# Dataforge-Pi.net
KiCad netlist of a schematic drawn in EAGLE
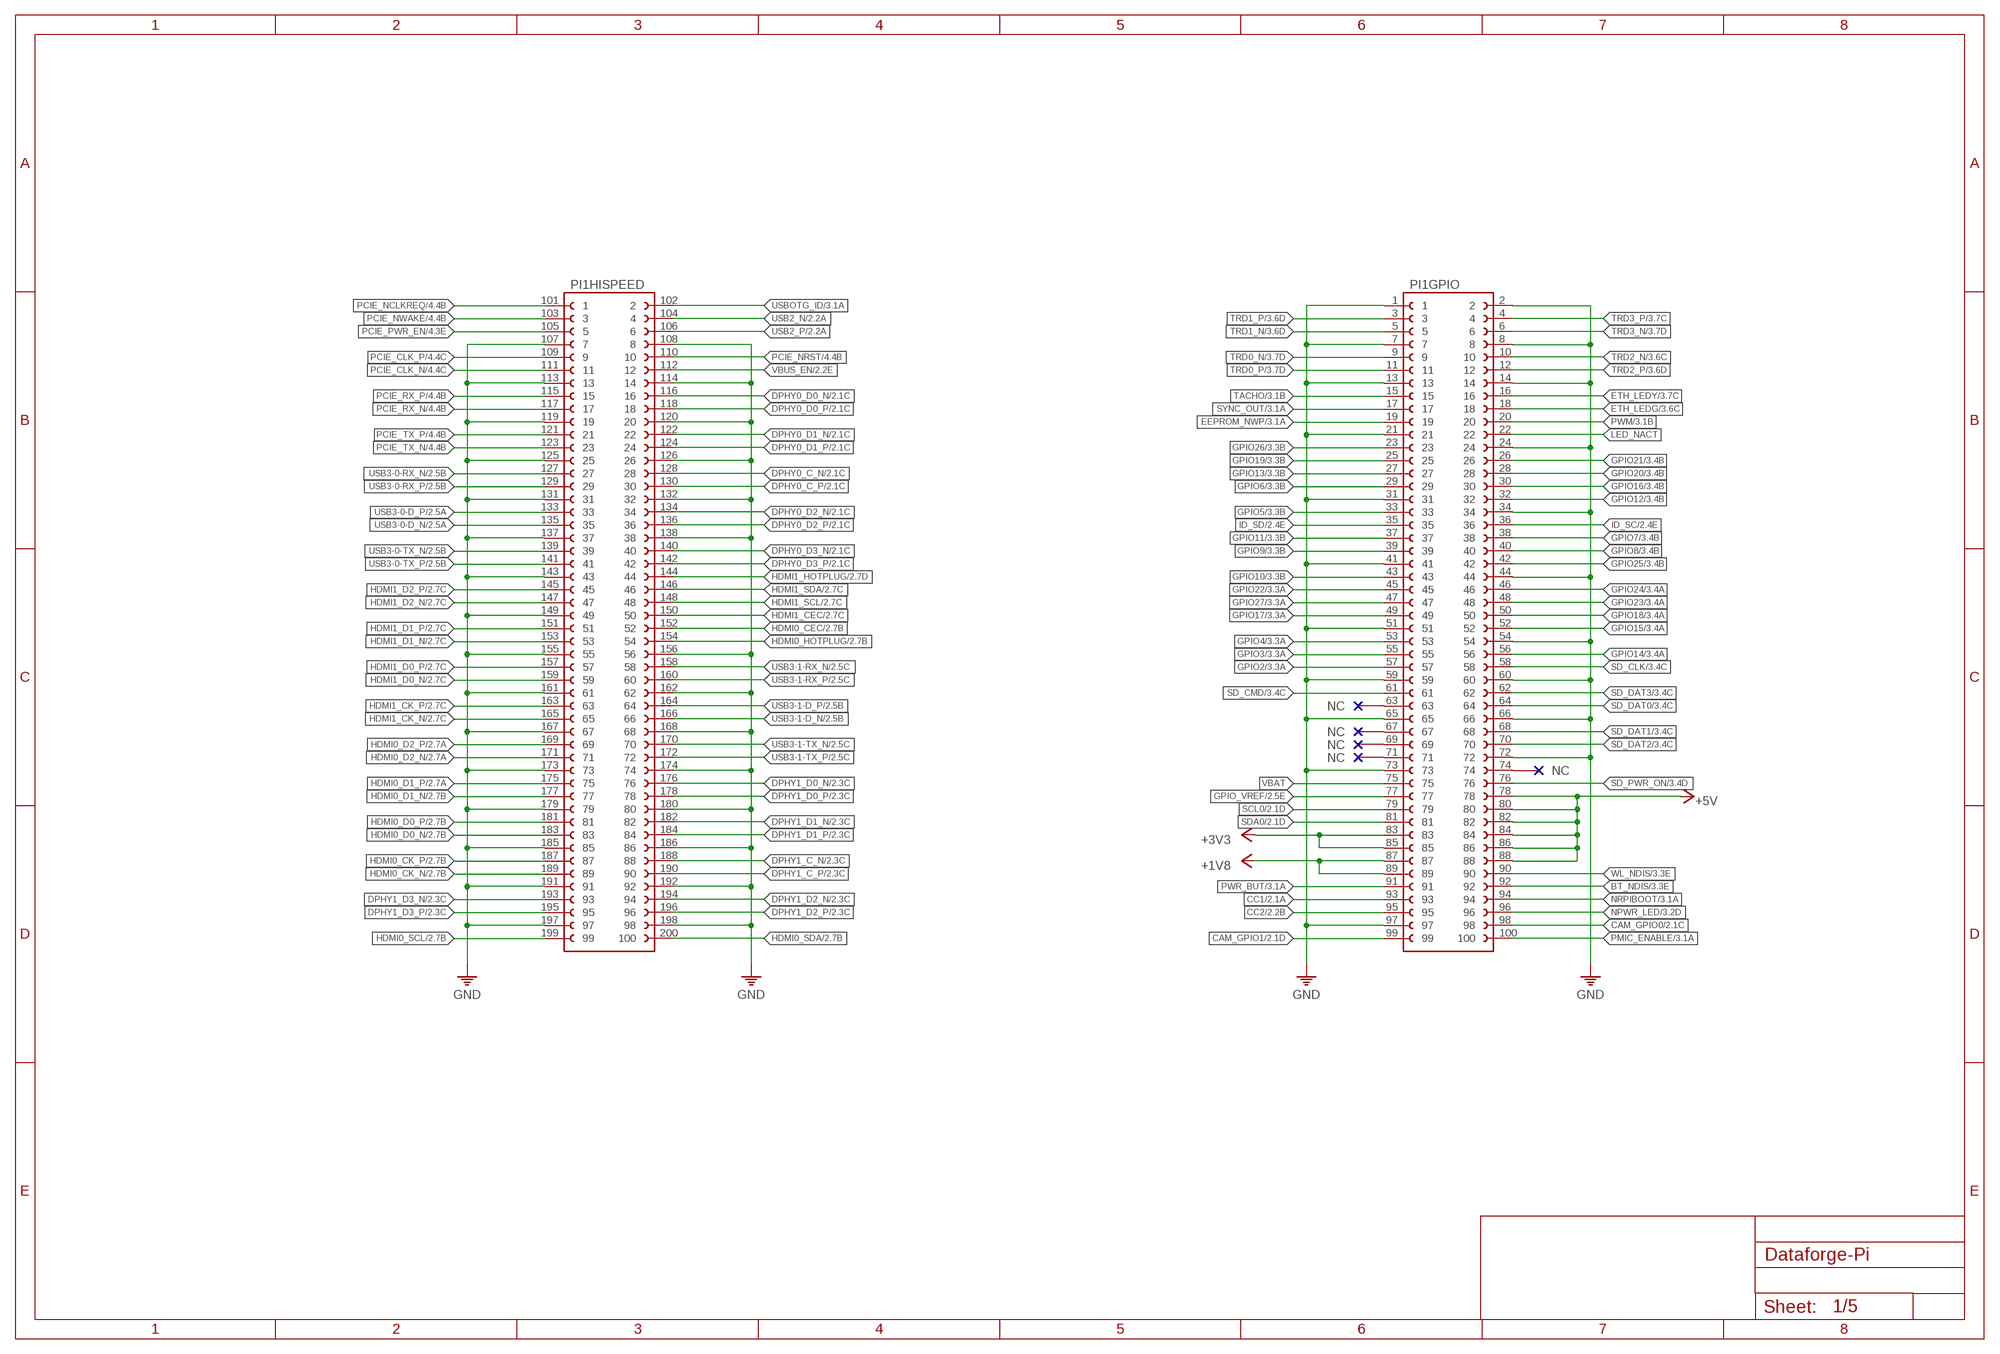
[diagram p0: schematic, sheet 1]
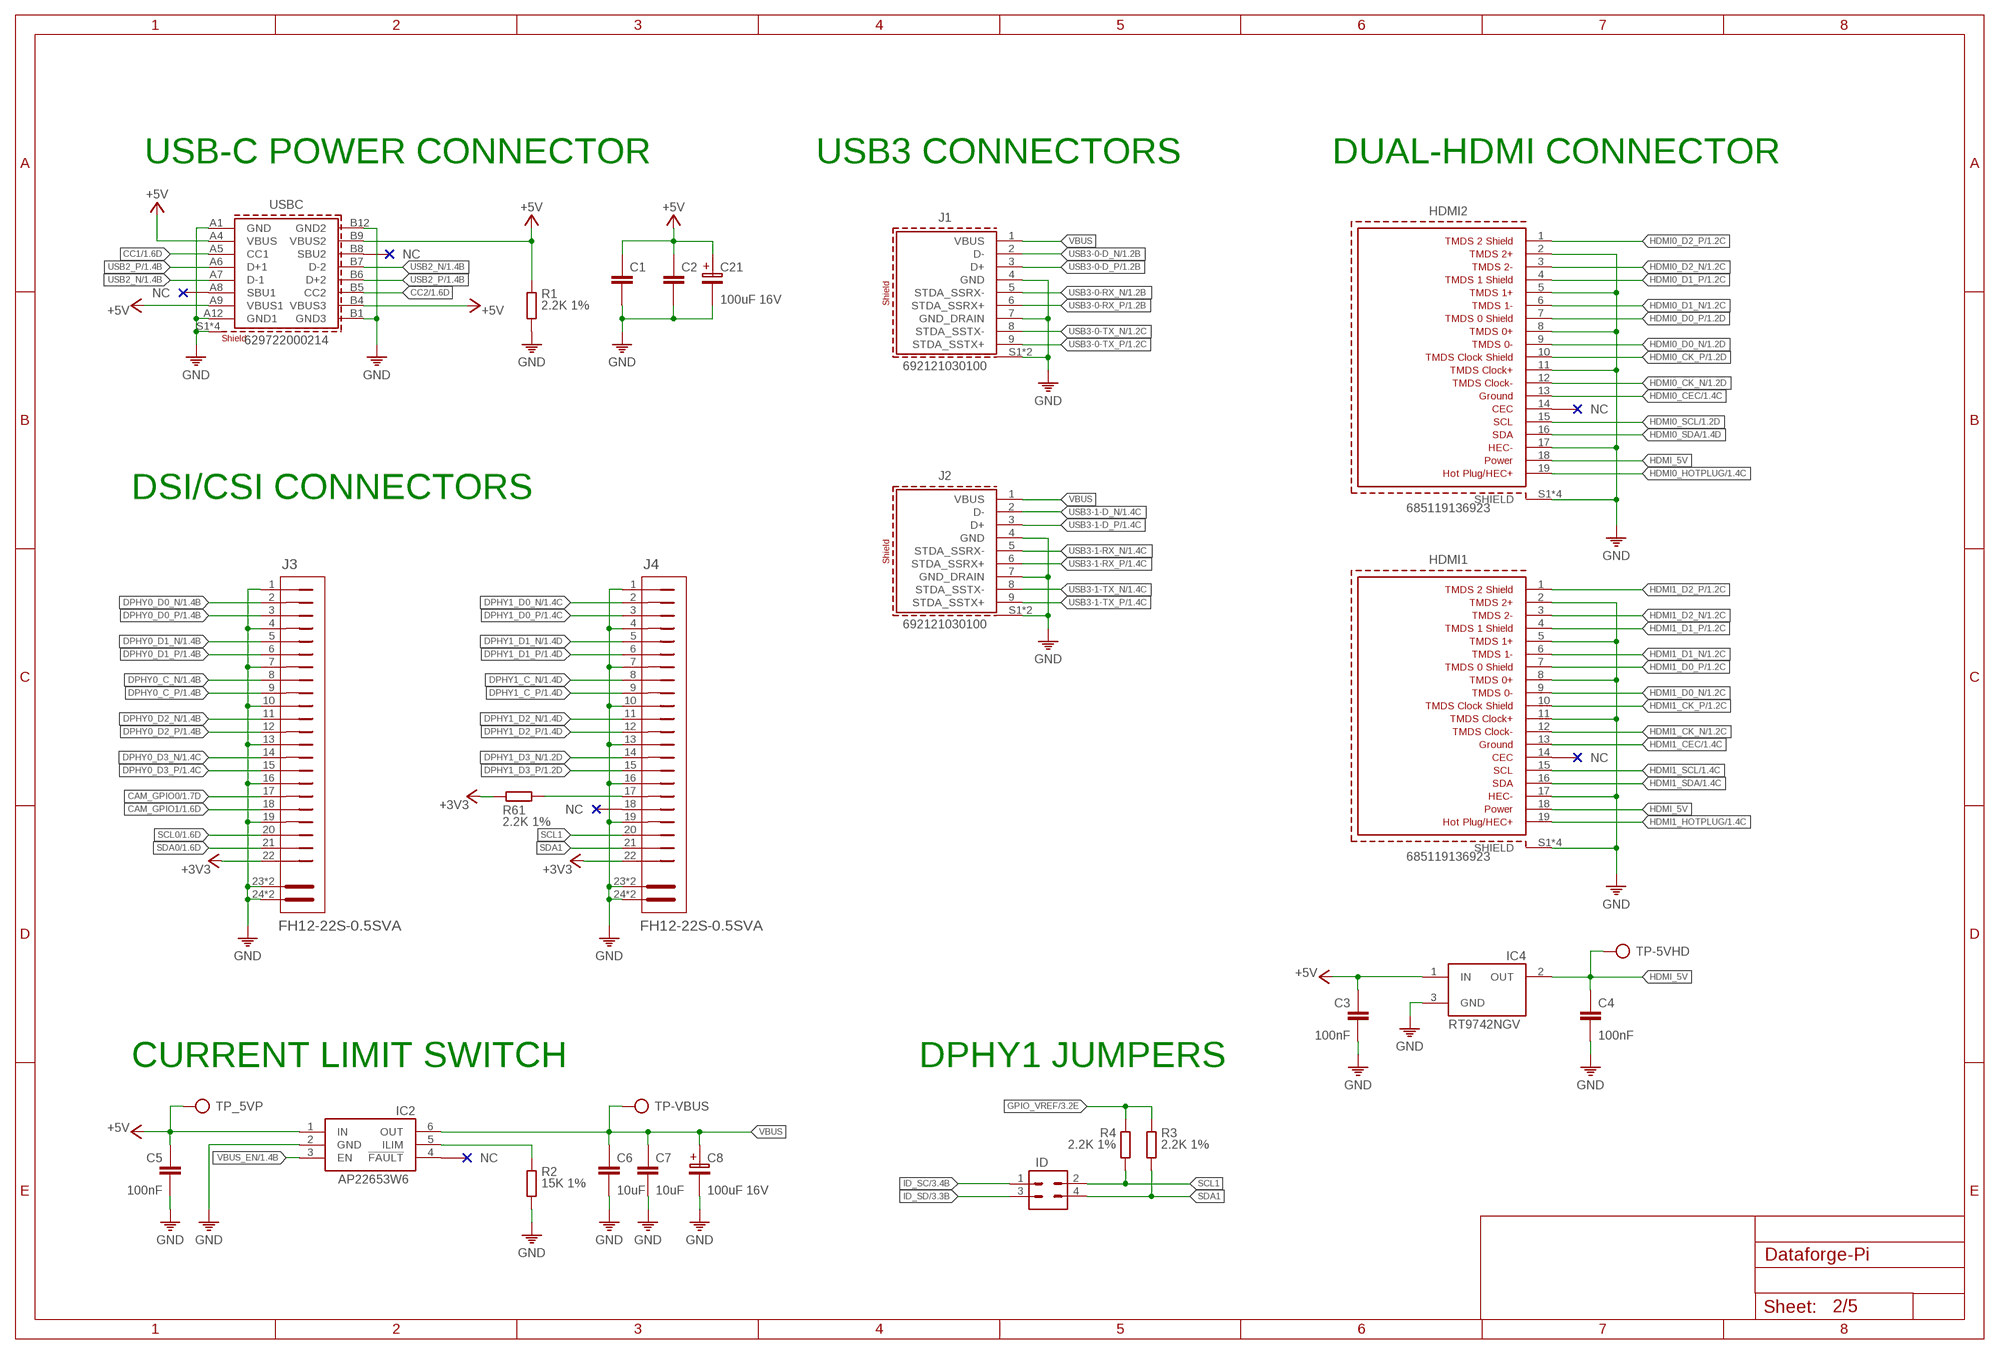
[diagram p1: schematic, sheet 2]
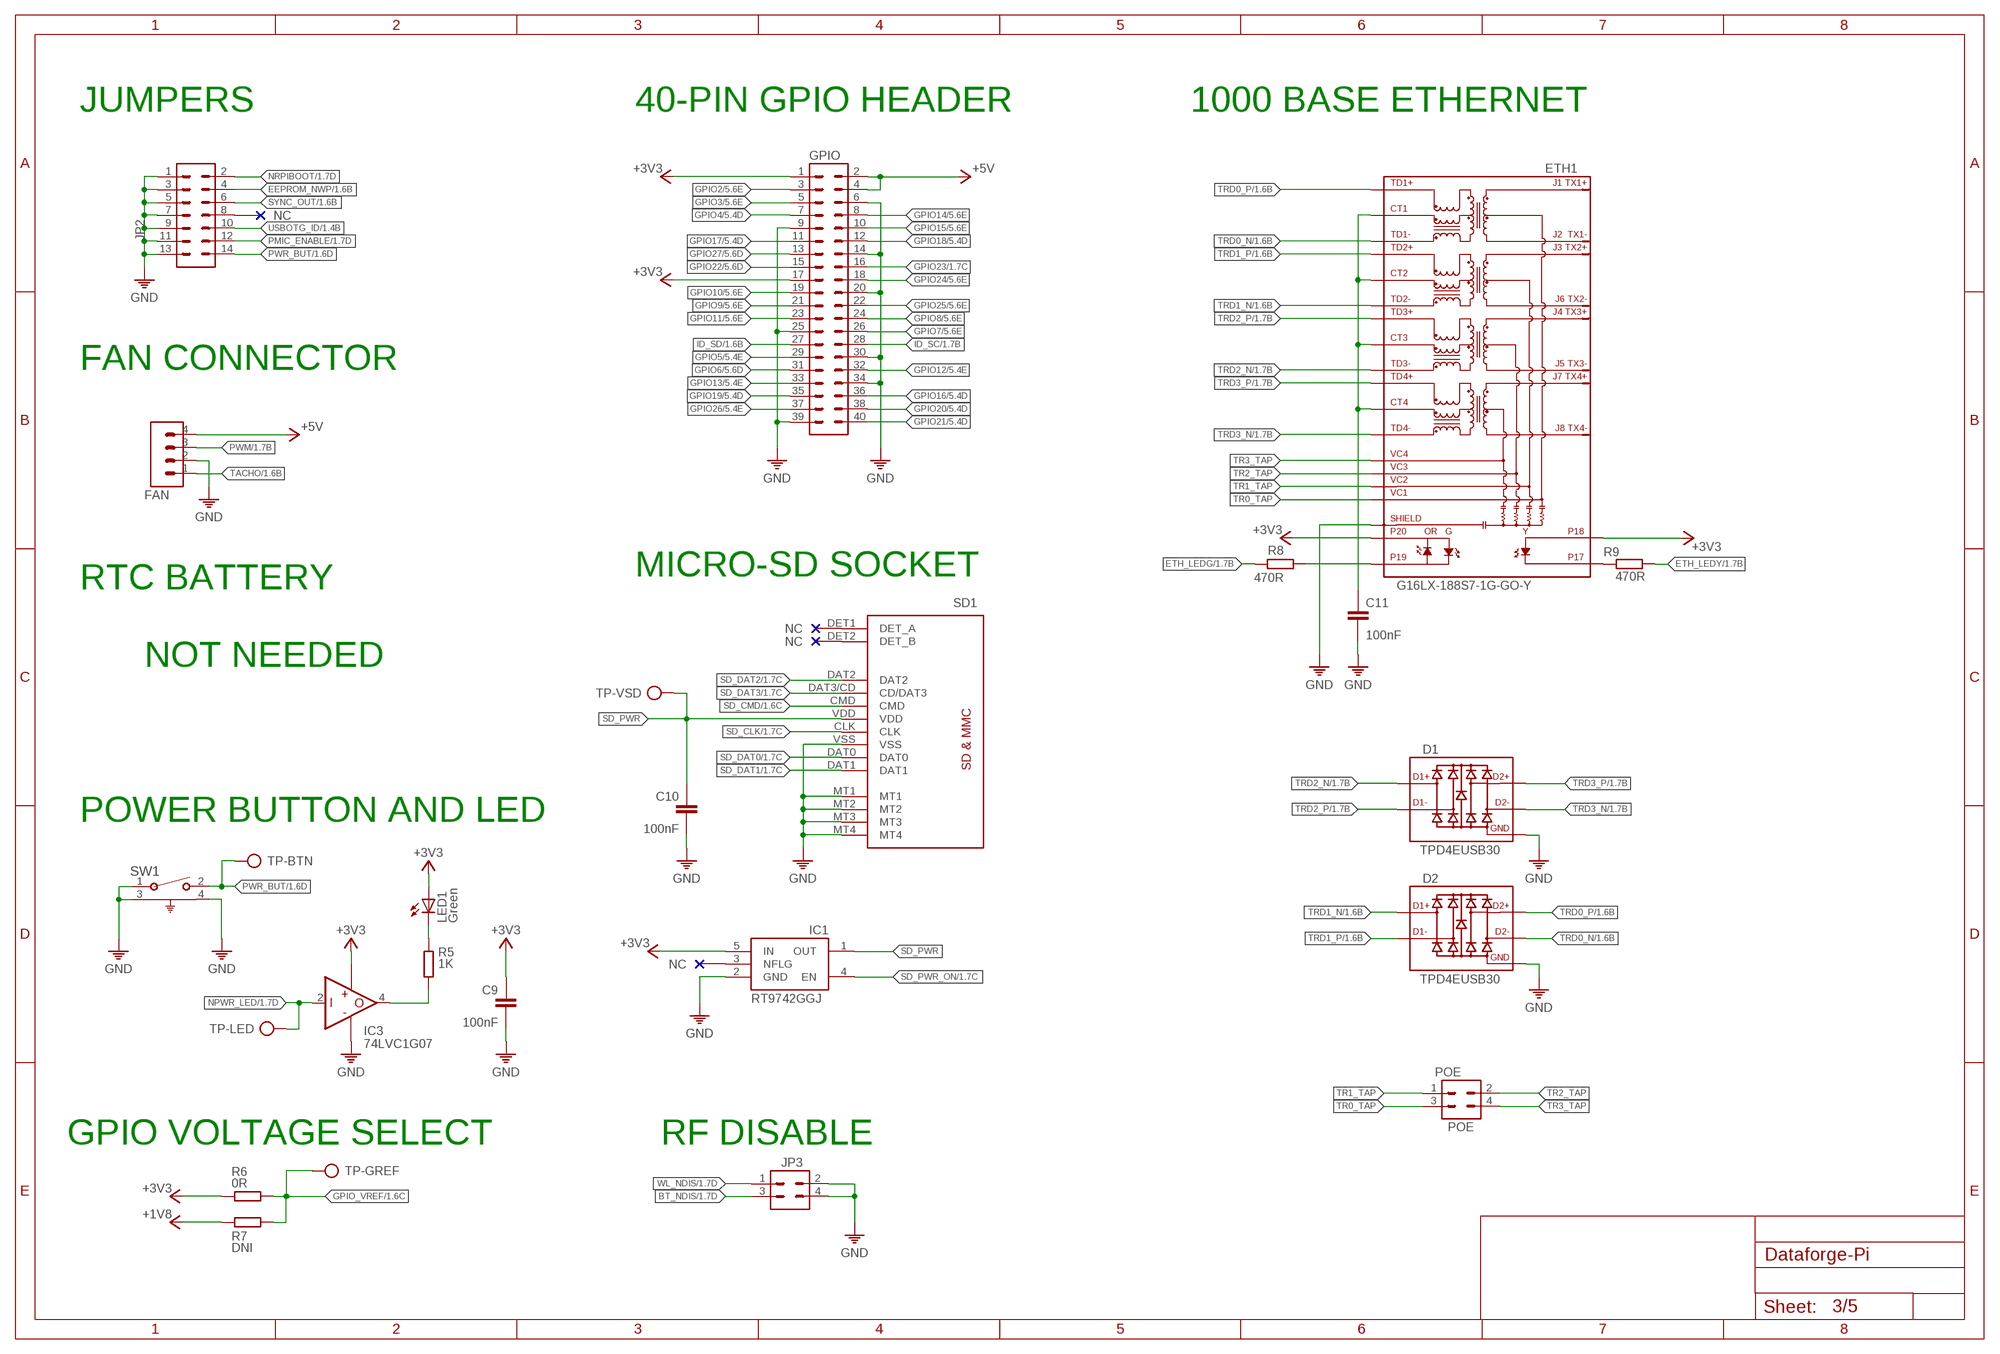
[diagram p2: schematic, sheet 3]
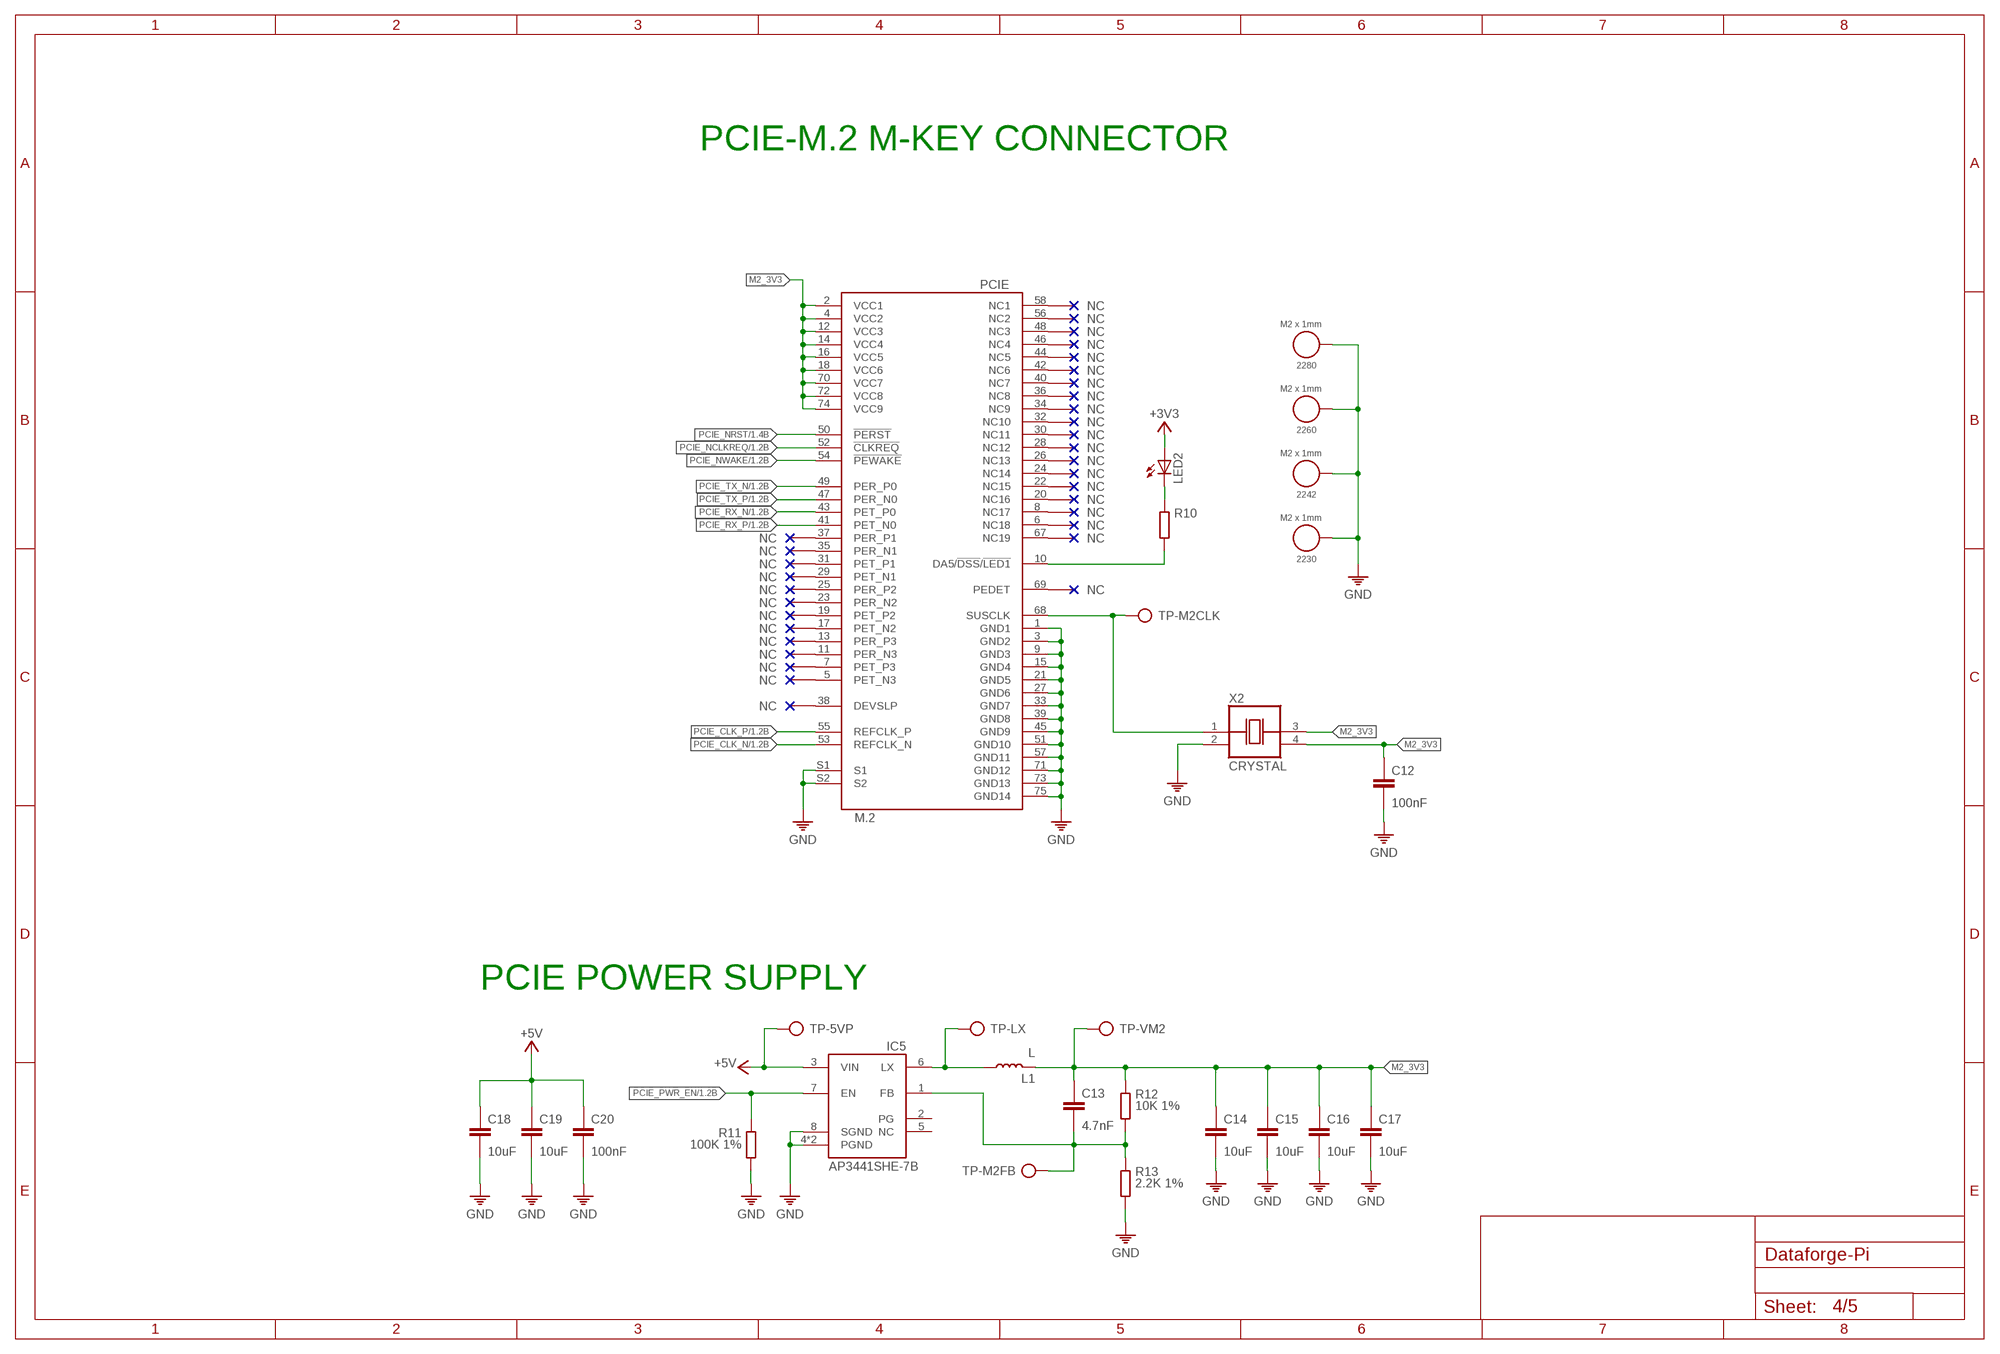
[diagram p3: schematic, sheet 4]
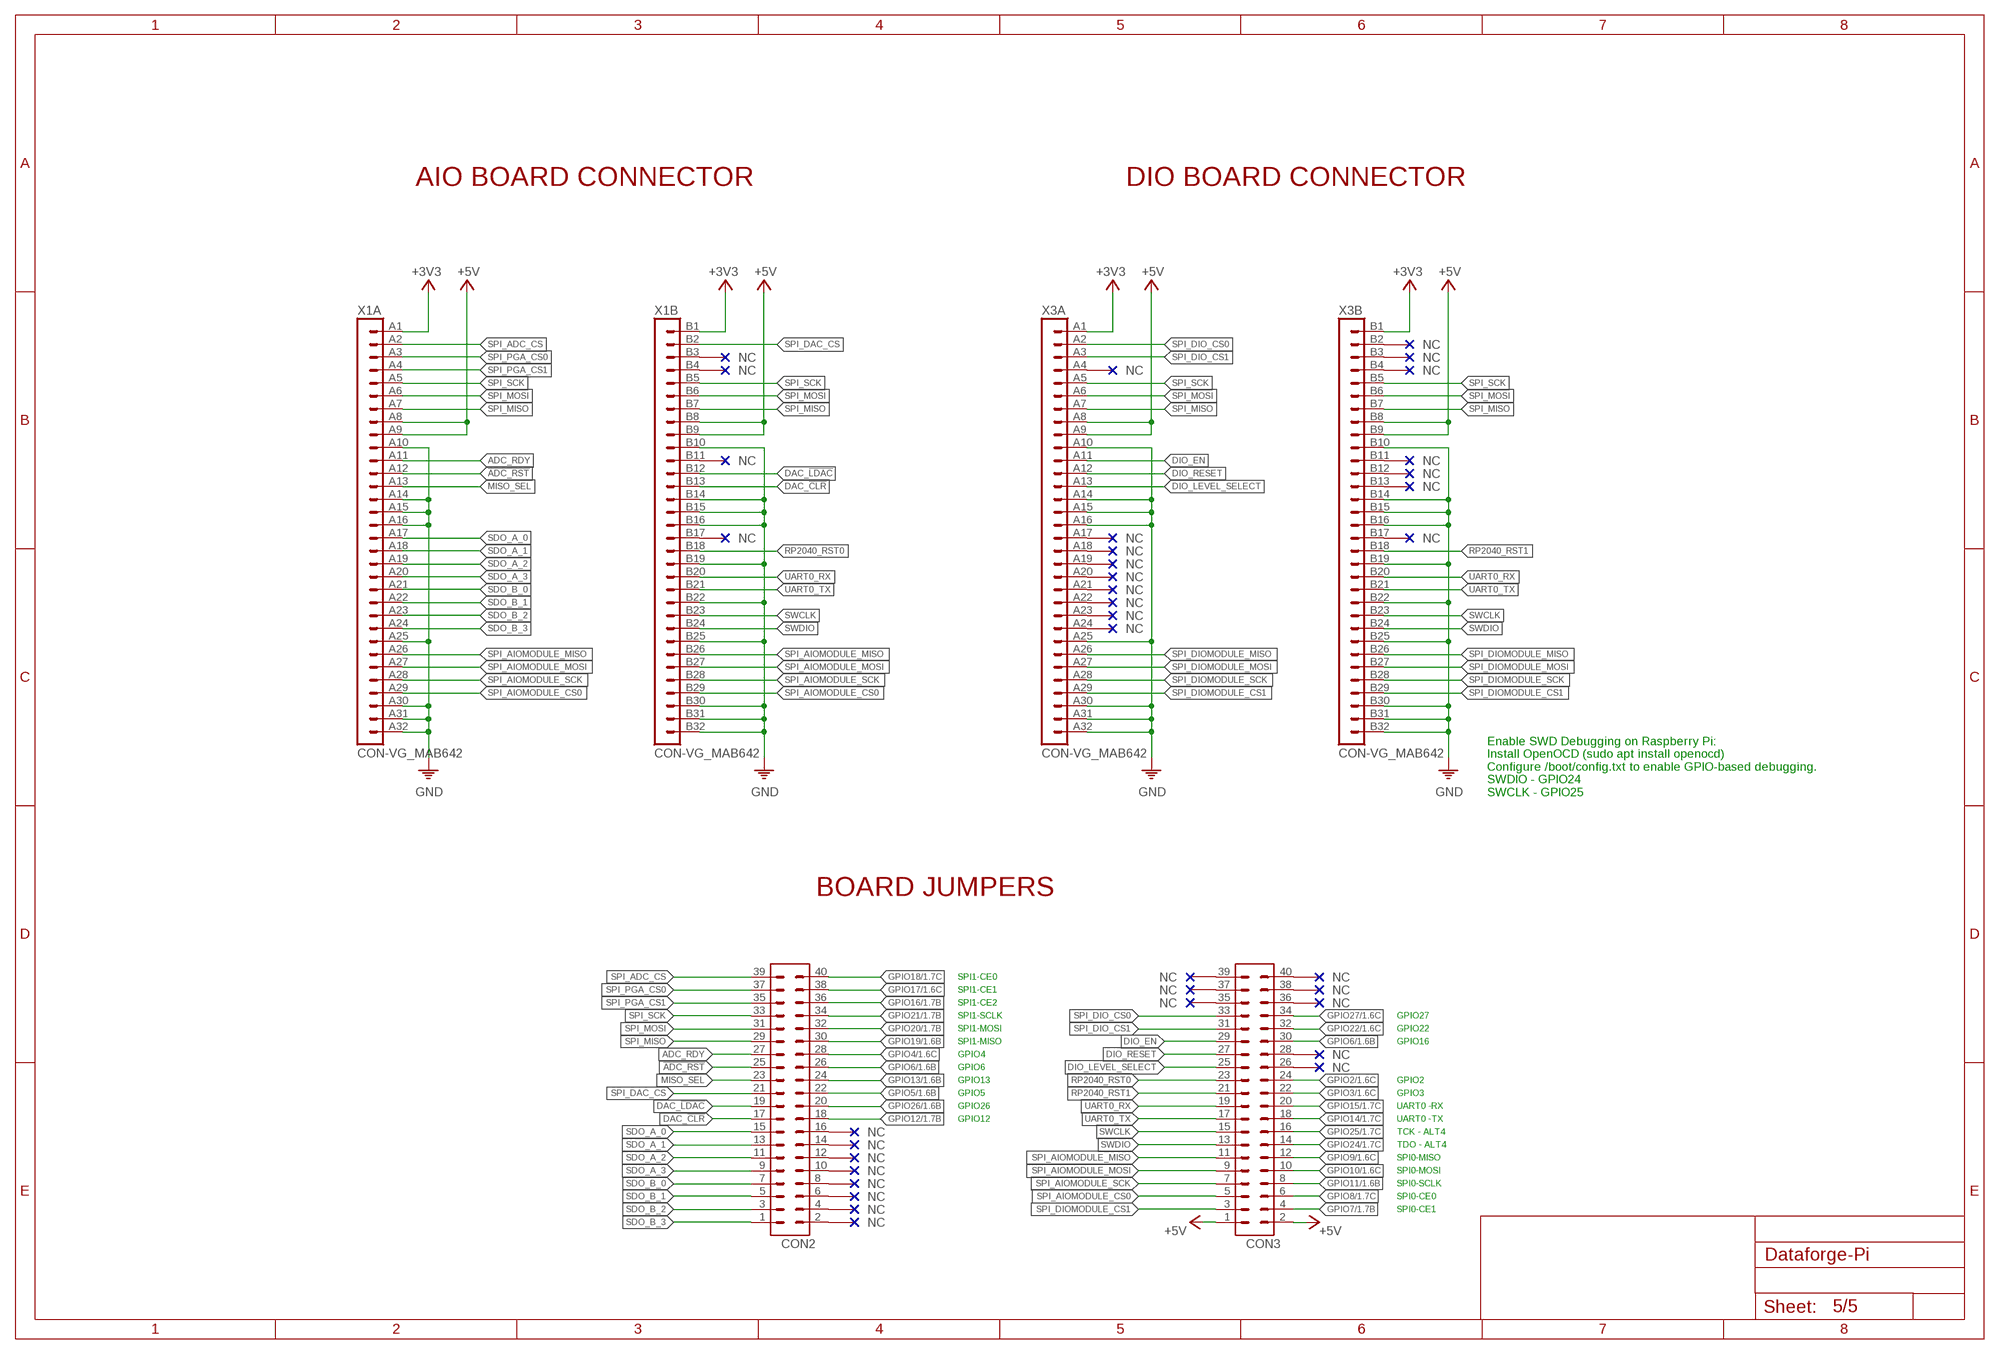
[diagram p4: schematic, sheet 5]

(export (version "E")
  (design (tool "Eeschema 10.0.6"))
  (components
    (comp (ref "C9")
      (value "100nF")
      (footprint "eagle-import:0402")
      (libsource (lib "eagle-import") (part "C0402"))
    )
    (comp (ref "C10")
      (value "100nF")
      (footprint "eagle-import:0402")
      (libsource (lib "eagle-import") (part "C0402"))
    )
    (comp (ref "C11")
      (value "100nF")
      (footprint "eagle-import:0402")
      (libsource (lib "eagle-import") (part "C0402"))
    )
    (comp (ref "D1")
      (value "TPD4EUSB30")
      (footprint "eagle-import:USON")
      (libsource (lib "eagle-import") (part "TPD4EUSB30"))
    )
    (comp (ref "D2")
      (value "TPD4EUSB30")
      (footprint "eagle-import:USON")
      (libsource (lib "eagle-import") (part "TPD4EUSB30"))
    )
    (comp (ref "ETH1")
      (value "G16LX-188S7-1G-GO-Y")
      (footprint "eagle-import:MAGJACK_POE")
      (libsource (lib "eagle-import") (part "MAGJACK-POE"))
    )
    (comp (ref "FAN")
      (value "CON-1X4")
      (footprint "eagle-import:1X4")
      (libsource (lib "eagle-import") (part "CON-1X4"))
    )
    (comp (ref "GPIO")
      (value "CON-2X20")
      (footprint "eagle-import:2X20")
      (libsource (lib "eagle-import") (part "CON-2X20"))
    )
    (comp (ref "IC1")
      (value "RT9742GGJ")
      (footprint "eagle-import:SOT23-5")
      (libsource (lib "eagle-import") (part "RT9742GGJ5"))
    )
    (comp (ref "IC3")
      (value "74LVC1G07")
      (footprint "eagle-import:SOT23-5")
      (libsource (lib "eagle-import") (part "74LVC1G07"))
    )
    (comp (ref "JP2")
      (value "CON-2X7")
      (footprint "eagle-import:2X7")
      (libsource (lib "eagle-import") (part "CON-2X7"))
    )
    (comp (ref "JP3")
      (value "CON-2X2")
      (footprint "eagle-import:2X2")
      (libsource (lib "eagle-import") (part "CON-2X2"))
    )
    (comp (ref "LED1")
      (value "Green")
      (footprint "eagle-import:CHIPLED_0805")
      (libsource (lib "eagle-import") (part "LEDCHIPLED_0805"))
    )
    (comp (ref "POE")
      (value "POE")
      (footprint "eagle-import:2X2")
      (libsource (lib "eagle-import") (part "CON-2X2"))
    )
    (comp (ref "R5")
      (value "1K")
      (footprint "eagle-import:0402")
      (libsource (lib "eagle-import") (part "R0402"))
    )
    (comp (ref "R6")
      (value "0R")
      (footprint "eagle-import:0402")
      (libsource (lib "eagle-import") (part "R0402"))
    )
    (comp (ref "R7")
      (value "DNI")
      (footprint "eagle-import:0402")
      (libsource (lib "eagle-import") (part "R0402"))
    )
    (comp (ref "R8")
      (value "470R")
      (footprint "eagle-import:0402")
      (libsource (lib "eagle-import") (part "R0402"))
    )
    (comp (ref "R9")
      (value "470R")
      (footprint "eagle-import:0402")
      (libsource (lib "eagle-import") (part "R0402"))
    )
    (comp (ref "SD1")
      (value "MICRO-SD")
      (footprint "eagle-import:MICROSD")
      (libsource (lib "eagle-import") (part "MICRO-SD"))
    )
    (comp (ref "SW1")
      (value "1825027-8")
      (footprint "eagle-import:SW2_1825027-C_TEC")
      (fields (field (name "COPYRIGHT") "Copyright (C) 2025 Ultra Librarian. All rights reserved."))
      (libsource (lib "eagle-import") (part "1825027-8"))
    )
    (comp (ref "TP-BTN")
      (value "TP")
      (footprint "eagle-import:TP")
      (libsource (lib "eagle-import") (part "TP"))
    )
    (comp (ref "TP-GREF")
      (value "TP")
      (footprint "eagle-import:TP")
      (libsource (lib "eagle-import") (part "TP"))
    )
    (comp (ref "TP-LED")
      (value "TP")
      (footprint "eagle-import:TP")
      (libsource (lib "eagle-import") (part "TP"))
    )
    (comp (ref "TP-VSD")
      (value "TP")
      (footprint "eagle-import:TP")
      (libsource (lib "eagle-import") (part "TP"))
    )
    (comp (ref "2230")
      (value "M2 x 1mm")
      (footprint "eagle-import:WA-SMSI_9774010243")
      (libsource (lib "eagle-import") (part "WA-SMSI_9774XXX243_9774010243"))
    )
    (comp (ref "2242")
      (value "M2 x 1mm")
      (footprint "eagle-import:WA-SMSI_9774010243")
      (libsource (lib "eagle-import") (part "WA-SMSI_9774XXX243_9774010243"))
    )
    (comp (ref "2260")
      (value "M2 x 1mm")
      (footprint "eagle-import:WA-SMSI_9774010243")
      (libsource (lib "eagle-import") (part "WA-SMSI_9774XXX243_9774010243"))
    )
    (comp (ref "2280")
      (value "M2 x 1mm")
      (footprint "eagle-import:WA-SMSI_9774010243")
      (libsource (lib "eagle-import") (part "WA-SMSI_9774XXX243_9774010243"))
    )
    (comp (ref "C12")
      (value "100nF")
      (footprint "eagle-import:0402")
      (libsource (lib "eagle-import") (part "C0402"))
    )
    (comp (ref "C13")
      (value "4.7nF")
      (footprint "eagle-import:0402")
      (libsource (lib "eagle-import") (part "C0402"))
    )
    (comp (ref "C14")
      (value "10uF")
      (footprint "eagle-import:0805")
      (libsource (lib "eagle-import") (part "C0805"))
    )
    (comp (ref "C15")
      (value "10uF")
      (footprint "eagle-import:0805")
      (libsource (lib "eagle-import") (part "C0805"))
    )
    (comp (ref "C16")
      (value "10uF")
      (footprint "eagle-import:0805")
      (libsource (lib "eagle-import") (part "C0805"))
    )
    (comp (ref "C17")
      (value "10uF")
      (footprint "eagle-import:0805")
      (libsource (lib "eagle-import") (part "C0805"))
    )
    (comp (ref "C18")
      (value "10uF")
      (footprint "eagle-import:0805")
      (libsource (lib "eagle-import") (part "C0805"))
    )
    (comp (ref "C19")
      (value "10uF")
      (footprint "eagle-import:0805")
      (libsource (lib "eagle-import") (part "C0805"))
    )
    (comp (ref "C20")
      (value "100nF")
      (footprint "eagle-import:0402")
      (libsource (lib "eagle-import") (part "C0402"))
    )
    (comp (ref "IC5")
      (value "AP3441SHE-7B")
      (footprint "eagle-import:SON50P201X201X56-9T90X170N")
      (libsource (lib "eagle-import") (part "AP3441SHE-7B"))
    )
    (comp (ref "L1")
      (value "L")
      (footprint "eagle-import:SRR5228A")
      (libsource (lib "eagle-import") (part "L"))
    )
    (comp (ref "LED2")
      (value "LEDCHIPLED_0805")
      (footprint "eagle-import:CHIPLED_0805")
      (libsource (lib "eagle-import") (part "LEDCHIPLED_0805"))
    )
    (comp (ref "PCIE")
      (value "M.2")
      (footprint "eagle-import:M.2")
      (libsource (lib "eagle-import") (part "M.2"))
    )
    (comp (ref "R10")
      (value "R0402")
      (footprint "eagle-import:0402")
      (libsource (lib "eagle-import") (part "R0402"))
    )
    (comp (ref "R11")
      (value "100K 1%")
      (footprint "eagle-import:0402")
      (libsource (lib "eagle-import") (part "R0402"))
    )
    (comp (ref "R12")
      (value "10K 1%")
      (footprint "eagle-import:0402")
      (libsource (lib "eagle-import") (part "R0402"))
    )
    (comp (ref "R13")
      (value "2.2K 1%")
      (footprint "eagle-import:0402")
      (libsource (lib "eagle-import") (part "R0402"))
    )
    (comp (ref "TP-5VP")
      (value "TP")
      (footprint "eagle-import:TP")
      (libsource (lib "eagle-import") (part "TP"))
    )
    (comp (ref "TP-LX")
      (value "TP")
      (footprint "eagle-import:TP")
      (libsource (lib "eagle-import") (part "TP"))
    )
    (comp (ref "TP-M2CLK")
      (value "TP")
      (footprint "eagle-import:TP")
      (libsource (lib "eagle-import") (part "TP"))
    )
    (comp (ref "TP-M2FB")
      (value "TP")
      (footprint "eagle-import:TP")
      (libsource (lib "eagle-import") (part "TP"))
    )
    (comp (ref "TP-VM2")
      (value "TP")
      (footprint "eagle-import:TP")
      (libsource (lib "eagle-import") (part "TP"))
    )
    (comp (ref "X2")
      (value "CRYSTAL")
      (footprint "eagle-import:OSCCC500X320X130")
      (libsource (lib "eagle-import") (part "CRYSTAL"))
    )
    (comp (ref "PI1")
      (value "RASPBERRY_CM5")
      (footprint "eagle-import:CM5")
      (libsource (lib "eagle-import") (part "RASPBERRY_CM5"))
    )
    (comp (ref "CON2")
      (value "CON-2X20")
      (footprint "eagle-import:2X20")
      (libsource (lib "eagle-import") (part "CON-2X20"))
    )
    (comp (ref "CON3")
      (value "CON-2X20")
      (footprint "eagle-import:2X20")
      (libsource (lib "eagle-import") (part "CON-2X20"))
    )
    (comp (ref "X1")
      (value "CON-VG_MAB642")
      (footprint "eagle-import:CON-VG-MAB64-RECEPTACLE")
      (libsource (lib "eagle-import") (part "CON-VG_MAB642"))
    )
    (comp (ref "X3")
      (value "CON-VG_MAB642")
      (footprint "eagle-import:CON-VG-MAB64-RECEPTACLE")
      (libsource (lib "eagle-import") (part "CON-VG_MAB642"))
    )
    (comp (ref "C1")
      (value "C0402")
      (footprint "eagle-import:0402")
      (libsource (lib "eagle-import") (part "C0402"))
    )
    (comp (ref "C2")
      (value "C0402")
      (footprint "eagle-import:0402")
      (libsource (lib "eagle-import") (part "C0402"))
    )
    (comp (ref "C3")
      (value "100nF")
      (footprint "eagle-import:0402")
      (libsource (lib "eagle-import") (part "C0402"))
    )
    (comp (ref "C4")
      (value "100nF")
      (footprint "eagle-import:0402")
      (libsource (lib "eagle-import") (part "C0402"))
    )
    (comp (ref "C5")
      (value "100nF")
      (footprint "eagle-import:0402")
      (libsource (lib "eagle-import") (part "C0402"))
    )
    (comp (ref "C6")
      (value "10uF")
      (footprint "eagle-import:0805")
      (libsource (lib "eagle-import") (part "C0805"))
    )
    (comp (ref "C7")
      (value "10uF")
      (footprint "eagle-import:0805")
      (libsource (lib "eagle-import") (part "C0805"))
    )
    (comp (ref "C8")
      (value "100uF 16V")
      (footprint "eagle-import:100UF-16V")
      (libsource (lib "eagle-import") (part "CPOL"))
    )
    (comp (ref "C21")
      (value "100uF 16V")
      (footprint "eagle-import:100UF-16V")
      (libsource (lib "eagle-import") (part "CPOL"))
    )
    (comp (ref "HDMI1")
      (value "685119136923")
      (footprint "eagle-import:685119136923")
      (libsource (lib "eagle-import") (part "685119136923"))
    )
    (comp (ref "HDMI2")
      (value "685119136923")
      (footprint "eagle-import:685119136923")
      (libsource (lib "eagle-import") (part "685119136923"))
    )
    (comp (ref "IC2")
      (value "AP22653W6")
      (footprint "eagle-import:SOT23-6")
      (libsource (lib "eagle-import") (part "AP22653W6"))
    )
    (comp (ref "IC4")
      (value "RT9742NGV")
      (footprint "eagle-import:SOT23")
      (libsource (lib "eagle-import") (part "RT9742NGV"))
    )
    (comp (ref "ID")
      (value "CON-2X2")
      (footprint "eagle-import:2X2")
      (libsource (lib "eagle-import") (part "CON-2X2"))
    )
    (comp (ref "J1")
      (value "692121030100")
      (footprint "eagle-import:692121030100")
      (libsource (lib "eagle-import") (part "692121030100"))
    )
    (comp (ref "J2")
      (value "692121030100")
      (footprint "eagle-import:692121030100")
      (libsource (lib "eagle-import") (part "692121030100"))
    )
    (comp (ref "J3")
      (value "FH12-22S-0.5SVA")
      (footprint "eagle-import:FH12-22S-0.5SH")
      (libsource (lib "eagle-import") (part "FH12-22S-0.5SVA"))
    )
    (comp (ref "J4")
      (value "FH12-22S-0.5SVA")
      (footprint "eagle-import:FH12-22S-0.5SH")
      (libsource (lib "eagle-import") (part "FH12-22S-0.5SVA"))
    )
    (comp (ref "R1")
      (value "2.2K 1%")
      (footprint "eagle-import:0402")
      (libsource (lib "eagle-import") (part "R0402"))
    )
    (comp (ref "R2")
      (value "15K 1%")
      (footprint "eagle-import:0402")
      (libsource (lib "eagle-import") (part "R0402"))
    )
    (comp (ref "R3")
      (value "2.2K 1%")
      (footprint "eagle-import:0402")
      (libsource (lib "eagle-import") (part "R0402"))
    )
    (comp (ref "R4")
      (value "2.2K 1%")
      (footprint "eagle-import:0402")
      (libsource (lib "eagle-import") (part "R0402"))
    )
    (comp (ref "R61")
      (value "2.2K 1%")
      (footprint "eagle-import:0402")
      (libsource (lib "eagle-import") (part "ds_passive_46685041_R0402"))
    )
    (comp (ref "TP-5VHD")
      (value "TP")
      (footprint "eagle-import:TP")
      (libsource (lib "eagle-import") (part "TP"))
    )
    (comp (ref "TP-VBUS")
      (value "TP")
      (footprint "eagle-import:TP")
      (libsource (lib "eagle-import") (part "TP"))
    )
    (comp (ref "TP_5VP")
      (value "TP")
      (footprint "eagle-import:TP")
      (libsource (lib "eagle-import") (part "TP"))
    )
    (comp (ref "USBC")
      (value "629722000214")
      (footprint "eagle-import:629722000214")
      (libsource (lib "eagle-import") (part "629722000214"))
    )
  )
  (nets
    (net (code "1") (name "+1V8") (class "Default")
      (node (ref "PI1") (pin "87") (pinfunction "87_87") (pintype "passive"))
      (node (ref "PI1") (pin "89") (pinfunction "89_89") (pintype "passive"))
      (node (ref "R7") (pin "1") (pinfunction "1_1") (pintype "passive"))
    )
    (net (code "2") (name "+3V3") (class "Default")
      (node (ref "C9") (pin "1") (pinfunction "1_1") (pintype "passive"))
      (node (ref "ETH1") (pin "18") (pinfunction "P18_18") (pintype "bidirectional"))
      (node (ref "ETH1") (pin "20") (pinfunction "P20_20") (pintype "bidirectional"))
      (node (ref "GPIO") (pin "1") (pinfunction "1_1") (pintype "bidirectional"))
      (node (ref "GPIO") (pin "17") (pinfunction "17_17") (pintype "bidirectional"))
      (node (ref "IC1") (pin "5") (pinfunction "IN_5") (pintype "power_in"))
      (node (ref "IC3") (pin "5") (pinfunction "VCC_5") (pintype "bidirectional"))
      (node (ref "J3") (pin "22") (pinfunction "22_22") (pintype "passive"))
      (node (ref "J4") (pin "22") (pinfunction "22_22") (pintype "passive"))
      (node (ref "LED1") (pin "A") (pinfunction "A_A") (pintype "passive"))
      (node (ref "LED2") (pin "A") (pinfunction "A_A") (pintype "passive"))
      (node (ref "PI1") (pin "83") (pinfunction "83_83") (pintype "passive"))
      (node (ref "PI1") (pin "85") (pinfunction "85_85") (pintype "passive"))
      (node (ref "R6") (pin "1") (pinfunction "1_1") (pintype "passive"))
      (node (ref "R61") (pin "2") (pinfunction "2_2") (pintype "passive"))
      (node (ref "X1") (pin "A1") (pinfunction "1_A1") (pintype "passive"))
      (node (ref "X1") (pin "B1") (pinfunction "1_B1") (pintype "passive"))
      (node (ref "X3") (pin "A1") (pinfunction "1_A1") (pintype "passive"))
      (node (ref "X3") (pin "B1") (pinfunction "1_B1") (pintype "passive"))
    )
    (net (code "3") (name "+5V") (class "Default")
      (node (ref "C1") (pin "1") (pinfunction "1_1") (pintype "passive"))
      (node (ref "C18") (pin "1") (pinfunction "1_1") (pintype "passive"))
      (node (ref "C19") (pin "1") (pinfunction "1_1") (pintype "passive"))
      (node (ref "C2") (pin "1") (pinfunction "1_1") (pintype "passive"))
      (node (ref "C20") (pin "1") (pinfunction "1_1") (pintype "passive"))
      (node (ref "C21") (pin "1") (pinfunction "1_1") (pintype "passive"))
      (node (ref "C3") (pin "1") (pinfunction "1_1") (pintype "passive"))
      (node (ref "C5") (pin "1") (pinfunction "1_1") (pintype "passive"))
      (node (ref "CON3") (pin "1") (pinfunction "1_1") (pintype "bidirectional"))
      (node (ref "CON3") (pin "2") (pinfunction "2_2") (pintype "bidirectional"))
      (node (ref "FAN") (pin "4") (pinfunction "P$4_4") (pintype "bidirectional"))
      (node (ref "GPIO") (pin "2") (pinfunction "2_2") (pintype "bidirectional"))
      (node (ref "GPIO") (pin "4") (pinfunction "4_4") (pintype "bidirectional"))
      (node (ref "IC2") (pin "1") (pinfunction "IN_1") (pintype "bidirectional"))
      (node (ref "IC4") (pin "1") (pinfunction "IN_1") (pintype "power_in"))
      (node (ref "IC5") (pin "3") (pinfunction "VIN_3") (pintype "power_in"))
      (node (ref "PI1") (pin "78") (pinfunction "78_78") (pintype "passive"))
      (node (ref "PI1") (pin "80") (pinfunction "80_80") (pintype "passive"))
      (node (ref "PI1") (pin "82") (pinfunction "82_82") (pintype "passive"))
      (node (ref "PI1") (pin "84") (pinfunction "84_84") (pintype "passive"))
      (node (ref "PI1") (pin "86") (pinfunction "86_86") (pintype "passive"))
      (node (ref "PI1") (pin "88") (pinfunction "88_88") (pintype "passive"))
      (node (ref "R1") (pin "1") (pinfunction "1_1") (pintype "passive"))
      (node (ref "TP-5VP") (pin "TP") (pinfunction "P$1_TP") (pintype "bidirectional"))
      (node (ref "TP_5VP") (pin "TP") (pinfunction "P$1_TP") (pintype "bidirectional"))
      (node (ref "USBC") (pin "A4") (pinfunction "VBUS_A4") (pintype "passive"))
      (node (ref "USBC") (pin "A9") (pinfunction "VBUS1_A9") (pintype "passive"))
      (node (ref "USBC") (pin "B4") (pinfunction "VBUS3_B4") (pintype "passive"))
      (node (ref "USBC") (pin "B9") (pinfunction "VBUS2_B9") (pintype "passive"))
      (node (ref "X1") (pin "A8") (pinfunction "8_A8") (pintype "passive"))
      (node (ref "X1") (pin "A9") (pinfunction "9_A9") (pintype "passive"))
      (node (ref "X1") (pin "B8") (pinfunction "8_B8") (pintype "passive"))
      (node (ref "X1") (pin "B9") (pinfunction "9_B9") (pintype "passive"))
      (node (ref "X3") (pin "A8") (pinfunction "8_A8") (pintype "passive"))
      (node (ref "X3") (pin "A9") (pinfunction "9_A9") (pintype "passive"))
      (node (ref "X3") (pin "B8") (pinfunction "8_B8") (pintype "passive"))
      (node (ref "X3") (pin "B9") (pinfunction "9_B9") (pintype "passive"))
    )
    (net (code "4") (name "ADC_RDY") (class "Default")
      (node (ref "CON2") (pin "27") (pinfunction "27_27") (pintype "bidirectional"))
      (node (ref "X1") (pin "A11") (pinfunction "11_A11") (pintype "passive"))
    )
    (net (code "5") (name "BT_NDIS") (class "Default")
      (node (ref "JP3") (pin "3") (pinfunction "3_3") (pintype "bidirectional"))
      (node (ref "PI1") (pin "92") (pinfunction "92_92") (pintype "passive"))
    )
    (net (code "6") (name "CAM_GPIO0") (class "Default")
      (node (ref "J3") (pin "17") (pinfunction "17_17") (pintype "passive"))
      (node (ref "PI1") (pin "98") (pinfunction "98_98") (pintype "passive"))
    )
    (net (code "7") (name "CAM_GPIO1") (class "Default")
      (node (ref "J3") (pin "18") (pinfunction "18_18") (pintype "passive"))
      (node (ref "PI1") (pin "99") (pinfunction "99_99") (pintype "passive"))
    )
    (net (code "8") (name "CC1") (class "Default")
      (node (ref "PI1") (pin "93") (pinfunction "93_93") (pintype "passive"))
      (node (ref "USBC") (pin "A5") (pinfunction "CC1_A5") (pintype "passive"))
    )
    (net (code "9") (name "CC2") (class "Default")
      (node (ref "PI1") (pin "95") (pinfunction "95_95") (pintype "passive"))
      (node (ref "USBC") (pin "B5") (pinfunction "CC2_B5") (pintype "passive"))
    )
    (net (code "10") (name "DAC_~{CLR}") (class "Default")
      (node (ref "CON2") (pin "17") (pinfunction "17_17") (pintype "bidirectional"))
      (node (ref "X1") (pin "B13") (pinfunction "13_B13") (pintype "passive"))
    )
    (net (code "11") (name "DAC_~{LDAC}") (class "Default")
      (node (ref "CON2") (pin "19") (pinfunction "19_19") (pintype "bidirectional"))
      (node (ref "X1") (pin "B12") (pinfunction "12_B12") (pintype "passive"))
    )
    (net (code "12") (name "DIO_EN") (class "Default")
      (node (ref "CON3") (pin "29") (pinfunction "29_29") (pintype "bidirectional"))
      (node (ref "X3") (pin "A11") (pinfunction "11_A11") (pintype "passive"))
    )
    (net (code "13") (name "DIO_LEVEL_SELECT") (class "Default")
      (node (ref "CON3") (pin "25") (pinfunction "25_25") (pintype "bidirectional"))
      (node (ref "X3") (pin "A13") (pinfunction "13_A13") (pintype "passive"))
    )
    (net (code "14") (name "DIO_RESET") (class "Default")
      (node (ref "CON3") (pin "27") (pinfunction "27_27") (pintype "bidirectional"))
      (node (ref "X3") (pin "A12") (pinfunction "12_A12") (pintype "passive"))
    )
    (net (code "15") (name "DPHY0_C_N") (class "Default")
      (node (ref "J3") (pin "8") (pinfunction "8_8") (pintype "passive"))
      (node (ref "PI1") (pin "128") (pinfunction "28_128") (pintype "passive"))
    )
    (net (code "16") (name "DPHY0_C_P") (class "Default")
      (node (ref "J3") (pin "9") (pinfunction "9_9") (pintype "passive"))
      (node (ref "PI1") (pin "130") (pinfunction "30_130") (pintype "passive"))
    )
    (net (code "17") (name "DPHY0_D0_N") (class "Default")
      (node (ref "J3") (pin "2") (pinfunction "2_2") (pintype "passive"))
      (node (ref "PI1") (pin "116") (pinfunction "16_116") (pintype "passive"))
    )
    (net (code "18") (name "DPHY0_D0_P") (class "Default")
      (node (ref "J3") (pin "3") (pinfunction "3_3") (pintype "passive"))
      (node (ref "PI1") (pin "118") (pinfunction "18_118") (pintype "passive"))
    )
    (net (code "19") (name "DPHY0_D1_N") (class "Default")
      (node (ref "J3") (pin "5") (pinfunction "5_5") (pintype "passive"))
      (node (ref "PI1") (pin "122") (pinfunction "22_122") (pintype "passive"))
    )
    (net (code "20") (name "DPHY0_D1_P") (class "Default")
      (node (ref "J3") (pin "6") (pinfunction "6_6") (pintype "passive"))
      (node (ref "PI1") (pin "124") (pinfunction "24_124") (pintype "passive"))
    )
    (net (code "21") (name "DPHY0_D2_N") (class "Default")
      (node (ref "J3") (pin "11") (pinfunction "11_11") (pintype "passive"))
      (node (ref "PI1") (pin "134") (pinfunction "34_134") (pintype "passive"))
    )
    (net (code "22") (name "DPHY0_D2_P") (class "Default")
      (node (ref "J3") (pin "12") (pinfunction "12_12") (pintype "passive"))
      (node (ref "PI1") (pin "136") (pinfunction "36_136") (pintype "passive"))
    )
    (net (code "23") (name "DPHY0_D3_N") (class "Default")
      (node (ref "J3") (pin "14") (pinfunction "14_14") (pintype "passive"))
      (node (ref "PI1") (pin "140") (pinfunction "40_140") (pintype "passive"))
    )
    (net (code "24") (name "DPHY0_D3_P") (class "Default")
      (node (ref "J3") (pin "15") (pinfunction "15_15") (pintype "passive"))
      (node (ref "PI1") (pin "142") (pinfunction "42_142") (pintype "passive"))
    )
    (net (code "25") (name "DPHY1_C_N") (class "Default")
      (node (ref "J4") (pin "8") (pinfunction "8_8") (pintype "passive"))
      (node (ref "PI1") (pin "188") (pinfunction "88_188") (pintype "passive"))
    )
    (net (code "26") (name "DPHY1_C_P") (class "Default")
      (node (ref "J4") (pin "9") (pinfunction "9_9") (pintype "passive"))
      (node (ref "PI1") (pin "190") (pinfunction "90_190") (pintype "passive"))
    )
    (net (code "27") (name "DPHY1_D0_N") (class "Default")
      (node (ref "J4") (pin "2") (pinfunction "2_2") (pintype "passive"))
      (node (ref "PI1") (pin "176") (pinfunction "76_176") (pintype "passive"))
    )
    (net (code "28") (name "DPHY1_D0_P") (class "Default")
      (node (ref "J4") (pin "3") (pinfunction "3_3") (pintype "passive"))
      (node (ref "PI1") (pin "178") (pinfunction "78_178") (pintype "passive"))
    )
    (net (code "29") (name "DPHY1_D1_N") (class "Default")
      (node (ref "J4") (pin "5") (pinfunction "5_5") (pintype "passive"))
      (node (ref "PI1") (pin "182") (pinfunction "82_182") (pintype "passive"))
    )
    (net (code "30") (name "DPHY1_D1_P") (class "Default")
      (node (ref "J4") (pin "6") (pinfunction "6_6") (pintype "passive"))
      (node (ref "PI1") (pin "184") (pinfunction "84_184") (pintype "passive"))
    )
    (net (code "31") (name "DPHY1_D2_N") (class "Default")
      (node (ref "J4") (pin "11") (pinfunction "11_11") (pintype "passive"))
      (node (ref "PI1") (pin "194") (pinfunction "94_194") (pintype "passive"))
    )
    (net (code "32") (name "DPHY1_D2_P") (class "Default")
      (node (ref "J4") (pin "12") (pinfunction "12_12") (pintype "passive"))
      (node (ref "PI1") (pin "196") (pinfunction "96_196") (pintype "passive"))
    )
    (net (code "33") (name "DPHY1_D3_N") (class "Default")
      (node (ref "J4") (pin "14") (pinfunction "14_14") (pintype "passive"))
      (node (ref "PI1") (pin "193") (pinfunction "93_193") (pintype "passive"))
    )
    (net (code "34") (name "DPHY1_D3_P") (class "Default")
      (node (ref "J4") (pin "15") (pinfunction "15_15") (pintype "passive"))
      (node (ref "PI1") (pin "195") (pinfunction "95_195") (pintype "passive"))
    )
    (net (code "35") (name "EEPROM_NWP") (class "Default")
      (node (ref "JP2") (pin "4") (pinfunction "4_4") (pintype "bidirectional"))
      (node (ref "PI1") (pin "19") (pinfunction "19_19") (pintype "passive"))
    )
    (net (code "36") (name "ETH_LEDG") (class "Default")
      (node (ref "PI1") (pin "18") (pinfunction "18_18") (pintype "passive"))
      (node (ref "R8") (pin "1") (pinfunction "1_1") (pintype "passive"))
    )
    (net (code "37") (name "ETH_LEDY") (class "Default")
      (node (ref "PI1") (pin "16") (pinfunction "16_16") (pintype "passive"))
      (node (ref "R9") (pin "2") (pinfunction "2_2") (pintype "passive"))
    )
    (net (code "38") (name "GND") (class "Default")
      (node (ref "2230") (pin "1") (pinfunction "1_1") (pintype "passive"))
      (node (ref "2242") (pin "1") (pinfunction "1_1") (pintype "passive"))
      (node (ref "2260") (pin "1") (pinfunction "1_1") (pintype "passive"))
      (node (ref "2280") (pin "1") (pinfunction "1_1") (pintype "passive"))
      (node (ref "C1") (pin "2") (pinfunction "2_2") (pintype "passive"))
      (node (ref "C10") (pin "2") (pinfunction "2_2") (pintype "passive"))
      (node (ref "C11") (pin "2") (pinfunction "2_2") (pintype "passive"))
      (node (ref "C12") (pin "2") (pinfunction "2_2") (pintype "passive"))
      (node (ref "C14") (pin "2") (pinfunction "2_2") (pintype "passive"))
      (node (ref "C15") (pin "2") (pinfunction "2_2") (pintype "passive"))
      (node (ref "C16") (pin "2") (pinfunction "2_2") (pintype "passive"))
      (node (ref "C17") (pin "2") (pinfunction "2_2") (pintype "passive"))
      (node (ref "C18") (pin "2") (pinfunction "2_2") (pintype "passive"))
      (node (ref "C19") (pin "2") (pinfunction "2_2") (pintype "passive"))
      (node (ref "C2") (pin "2") (pinfunction "2_2") (pintype "passive"))
      (node (ref "C20") (pin "2") (pinfunction "2_2") (pintype "passive"))
      (node (ref "C21") (pin "2") (pinfunction "2_2") (pintype "passive"))
      (node (ref "C3") (pin "2") (pinfunction "2_2") (pintype "passive"))
      (node (ref "C4") (pin "2") (pinfunction "2_2") (pintype "passive"))
      (node (ref "C5") (pin "2") (pinfunction "2_2") (pintype "passive"))
      (node (ref "C6") (pin "2") (pinfunction "2_2") (pintype "passive"))
      (node (ref "C7") (pin "2") (pinfunction "2_2") (pintype "passive"))
      (node (ref "C8") (pin "2") (pinfunction "2_2") (pintype "passive"))
      (node (ref "C9") (pin "2") (pinfunction "2_2") (pintype "passive"))
      (node (ref "D1") (pin "3") (pinfunction "GND_3") (pintype "bidirectional"))
      (node (ref "D1") (pin "8") (pinfunction "GND_8") (pintype "bidirectional"))
      (node (ref "D2") (pin "3") (pinfunction "GND_3") (pintype "bidirectional"))
      (node (ref "D2") (pin "8") (pinfunction "GND_8") (pintype "bidirectional"))
      (node (ref "ETH1") (pin "MH3") (pinfunction "SHIELD_MH3") (pintype "bidirectional"))
      (node (ref "ETH1") (pin "MH4") (pinfunction "SHIELD_MH4") (pintype "bidirectional"))
      (node (ref "FAN") (pin "2") (pinfunction "P$2_2") (pintype "bidirectional"))
      (node (ref "GPIO") (pin "14") (pinfunction "14_14") (pintype "bidirectional"))
      (node (ref "GPIO") (pin "20") (pinfunction "20_20") (pintype "bidirectional"))
      (node (ref "GPIO") (pin "25") (pinfunction "25_25") (pintype "bidirectional"))
      (node (ref "GPIO") (pin "30") (pinfunction "30_30") (pintype "bidirectional"))
      (node (ref "GPIO") (pin "34") (pinfunction "34_34") (pintype "bidirectional"))
      (node (ref "GPIO") (pin "39") (pinfunction "39_39") (pintype "bidirectional"))
      (node (ref "GPIO") (pin "6") (pinfunction "6_6") (pintype "bidirectional"))
      (node (ref "GPIO") (pin "9") (pinfunction "9_9") (pintype "bidirectional"))
      (node (ref "HDMI1") (pin "11") (pinfunction "TMDSCLOCK+_11") (pintype "passive"))
      (node (ref "HDMI1") (pin "17") (pinfunction "UTILITY/HEAC+_17") (pintype "passive"))
      (node (ref "HDMI1") (pin "2") (pinfunction "TMDS2+_2") (pintype "passive"))
      (node (ref "HDMI1") (pin "5") (pinfunction "TMDSDATA1+_5") (pintype "passive"))
      (node (ref "HDMI1") (pin "8") (pinfunction "TMDS0+_8") (pintype "passive"))
      (node (ref "HDMI1") (pin "S1") (pinfunction "SHIELD_S1") (pintype "passive"))
      (node (ref "HDMI1") (pin "S2") (pinfunction "SHIELD_S2") (pintype "passive"))
      (node (ref "HDMI1") (pin "S3") (pinfunction "SHIELD_S3") (pintype "passive"))
      (node (ref "HDMI1") (pin "S4") (pinfunction "SHIELD_S4") (pintype "passive"))
      (node (ref "HDMI2") (pin "11") (pinfunction "TMDSCLOCK+_11") (pintype "passive"))
      (node (ref "HDMI2") (pin "17") (pinfunction "UTILITY/HEAC+_17") (pintype "passive"))
      (node (ref "HDMI2") (pin "2") (pinfunction "TMDS2+_2") (pintype "passive"))
      (node (ref "HDMI2") (pin "5") (pinfunction "TMDSDATA1+_5") (pintype "passive"))
      (node (ref "HDMI2") (pin "8") (pinfunction "TMDS0+_8") (pintype "passive"))
      (node (ref "HDMI2") (pin "S1") (pinfunction "SHIELD_S1") (pintype "passive"))
      (node (ref "HDMI2") (pin "S2") (pinfunction "SHIELD_S2") (pintype "passive"))
      (node (ref "HDMI2") (pin "S3") (pinfunction "SHIELD_S3") (pintype "passive"))
      (node (ref "HDMI2") (pin "S4") (pinfunction "SHIELD_S4") (pintype "passive"))
      (node (ref "IC1") (pin "2") (pinfunction "GND_2") (pintype "power_in"))
      (node (ref "IC2") (pin "2") (pinfunction "GND_2") (pintype "bidirectional"))
      (node (ref "IC3") (pin "3") (pinfunction "GND_3") (pintype "bidirectional"))
      (node (ref "IC4") (pin "3") (pinfunction "GND_3") (pintype "power_in"))
      (node (ref "IC5") (pin "4") (pinfunction "PGND_4") (pintype "power_in"))
      (node (ref "IC5") (pin "8") (pinfunction "SGND_8") (pintype "power_in"))
      (node (ref "IC5") (pin "9") (pinfunction "PGND_9") (pintype "power_in"))
      (node (ref "J1") (pin "4") (pinfunction "GND_4") (pintype "passive"))
      (node (ref "J1") (pin "7") (pinfunction "GND_DRAIN_7") (pintype "passive"))
      (node (ref "J1") (pin "S1") (pinfunction "SHIELD_S1") (pintype "passive"))
      (node (ref "J1") (pin "S2") (pinfunction "SHIELD_S2") (pintype "passive"))
      (node (ref "J2") (pin "4") (pinfunction "GND_4") (pintype "passive"))
      (node (ref "J2") (pin "7") (pinfunction "GND_DRAIN_7") (pintype "passive"))
      (node (ref "J2") (pin "S1") (pinfunction "SHIELD_S1") (pintype "passive"))
      (node (ref "J2") (pin "S2") (pinfunction "SHIELD_S2") (pintype "passive"))
      (node (ref "J3") (pin "1") (pinfunction "1_1") (pintype "passive"))
      (node (ref "J3") (pin "10") (pinfunction "10_10") (pintype "passive"))
      (node (ref "J3") (pin "13") (pinfunction "13_13") (pintype "passive"))
      (node (ref "J3") (pin "16") (pinfunction "16_16") (pintype "passive"))
      (node (ref "J3") (pin "19") (pinfunction "19_19") (pintype "passive"))
      (node (ref "J3") (pin "23") (pinfunction "MH1_23") (pintype "passive"))
      (node (ref "J3") (pin "24") (pinfunction "MH2_24") (pintype "passive"))
      (node (ref "J3") (pin "25") (pinfunction "MH1_25") (pintype "passive"))
      (node (ref "J3") (pin "26") (pinfunction "MH2_26") (pintype "passive"))
      (node (ref "J3") (pin "4") (pinfunction "4_4") (pintype "passive"))
      (node (ref "J3") (pin "7") (pinfunction "7_7") (pintype "passive"))
      (node (ref "J4") (pin "1") (pinfunction "1_1") (pintype "passive"))
      (node (ref "J4") (pin "10") (pinfunction "10_10") (pintype "passive"))
      (node (ref "J4") (pin "13") (pinfunction "13_13") (pintype "passive"))
      (node (ref "J4") (pin "16") (pinfunction "16_16") (pintype "passive"))
      (node (ref "J4") (pin "19") (pinfunction "19_19") (pintype "passive"))
      (node (ref "J4") (pin "23") (pinfunction "MH1_23") (pintype "passive"))
      (node (ref "J4") (pin "24") (pinfunction "MH2_24") (pintype "passive"))
      (node (ref "J4") (pin "25") (pinfunction "MH1_25") (pintype "passive"))
      (node (ref "J4") (pin "26") (pinfunction "MH2_26") (pintype "passive"))
      (node (ref "J4") (pin "4") (pinfunction "4_4") (pintype "passive"))
      (node (ref "J4") (pin "7") (pinfunction "7_7") (pintype "passive"))
      (node (ref "JP2") (pin "1") (pinfunction "1_1") (pintype "bidirectional"))
      (node (ref "JP2") (pin "11") (pinfunction "11_11") (pintype "bidirectional"))
      (node (ref "JP2") (pin "13") (pinfunction "13_13") (pintype "bidirectional"))
      (node (ref "JP2") (pin "3") (pinfunction "3_3") (pintype "bidirectional"))
      (node (ref "JP2") (pin "5") (pinfunction "5_5") (pintype "bidirectional"))
      (node (ref "JP2") (pin "7") (pinfunction "7_7") (pintype "bidirectional"))
      (node (ref "JP2") (pin "9") (pinfunction "9_9") (pintype "bidirectional"))
      (node (ref "JP3") (pin "2") (pinfunction "2_2") (pintype "bidirectional"))
      (node (ref "JP3") (pin "4") (pinfunction "4_4") (pintype "bidirectional"))
      (node (ref "PCIE") (pin "1") (pinfunction "GND1_1") (pintype "bidirectional"))
      (node (ref "PCIE") (pin "15") (pinfunction "GND4_15") (pintype "bidirectional"))
      (node (ref "PCIE") (pin "21") (pinfunction "GND5_21") (pintype "bidirectional"))
      (node (ref "PCIE") (pin "27") (pinfunction "GND6_27") (pintype "bidirectional"))
      (node (ref "PCIE") (pin "3") (pinfunction "GND2_3") (pintype "bidirectional"))
      (node (ref "PCIE") (pin "33") (pinfunction "GND7_33") (pintype "bidirectional"))
      (node (ref "PCIE") (pin "39") (pinfunction "GND8_39") (pintype "bidirectional"))
      (node (ref "PCIE") (pin "45") (pinfunction "GND9_45") (pintype "bidirectional"))
      (node (ref "PCIE") (pin "51") (pinfunction "GND10_51") (pintype "bidirectional"))
      (node (ref "PCIE") (pin "57") (pinfunction "GND11_57") (pintype "bidirectional"))
      (node (ref "PCIE") (pin "71") (pinfunction "GND12_71") (pintype "bidirectional"))
      (node (ref "PCIE") (pin "73") (pinfunction "GND13_73") (pintype "bidirectional"))
      (node (ref "PCIE") (pin "75") (pinfunction "GND14_75") (pintype "bidirectional"))
      (node (ref "PCIE") (pin "9") (pinfunction "GND3_9") (pintype "bidirectional"))
      (node (ref "PCIE") (pin "S1") (pinfunction "S1_S1") (pintype "bidirectional"))
      (node (ref "PCIE") (pin "S2") (pinfunction "S2_S2") (pintype "bidirectional"))
      (node (ref "PI1") (pin "1") (pinfunction "1_1") (pintype "passive"))
      (node (ref "PI1") (pin "107") (pinfunction "7_107") (pintype "passive"))
      (node (ref "PI1") (pin "108") (pinfunction "8_108") (pintype "passive"))
      (node (ref "PI1") (pin "113") (pinfunction "13_113") (pintype "passive"))
      (node (ref "PI1") (pin "114") (pinfunction "14_114") (pintype "passive"))
      (node (ref "PI1") (pin "119") (pinfunction "19_119") (pintype "passive"))
      (node (ref "PI1") (pin "120") (pinfunction "20_120") (pintype "passive"))
      (node (ref "PI1") (pin "125") (pinfunction "25_125") (pintype "passive"))
      (node (ref "PI1") (pin "126") (pinfunction "26_126") (pintype "passive"))
      (node (ref "PI1") (pin "13") (pinfunction "13_13") (pintype "passive"))
      (node (ref "PI1") (pin "131") (pinfunction "31_131") (pintype "passive"))
      (node (ref "PI1") (pin "132") (pinfunction "32_132") (pintype "passive"))
      (node (ref "PI1") (pin "137") (pinfunction "37_137") (pintype "passive"))
      (node (ref "PI1") (pin "138") (pinfunction "38_138") (pintype "passive"))
      (node (ref "PI1") (pin "14") (pinfunction "14_14") (pintype "passive"))
      (node (ref "PI1") (pin "143") (pinfunction "43_143") (pintype "passive"))
      (node (ref "PI1") (pin "149") (pinfunction "49_149") (pintype "passive"))
      (node (ref "PI1") (pin "155") (pinfunction "55_155") (pintype "passive"))
      (node (ref "PI1") (pin "156") (pinfunction "56_156") (pintype "passive"))
      (node (ref "PI1") (pin "161") (pinfunction "61_161") (pintype "passive"))
      (node (ref "PI1") (pin "162") (pinfunction "62_162") (pintype "passive"))
      (node (ref "PI1") (pin "167") (pinfunction "67_167") (pintype "passive"))
      (node (ref "PI1") (pin "168") (pinfunction "68_168") (pintype "passive"))
      (node (ref "PI1") (pin "173") (pinfunction "73_173") (pintype "passive"))
      (node (ref "PI1") (pin "174") (pinfunction "74_174") (pintype "passive"))
      (node (ref "PI1") (pin "179") (pinfunction "79_179") (pintype "passive"))
      (node (ref "PI1") (pin "180") (pinfunction "80_180") (pintype "passive"))
      (node (ref "PI1") (pin "185") (pinfunction "85_185") (pintype "passive"))
      (node (ref "PI1") (pin "186") (pinfunction "86_186") (pintype "passive"))
      (node (ref "PI1") (pin "191") (pinfunction "91_191") (pintype "passive"))
      (node (ref "PI1") (pin "192") (pinfunction "92_192") (pintype "passive"))
      (node (ref "PI1") (pin "197") (pinfunction "97_197") (pintype "passive"))
      (node (ref "PI1") (pin "198") (pinfunction "98_198") (pintype "passive"))
      (node (ref "PI1") (pin "2") (pinfunction "2_2") (pintype "passive"))
      (node (ref "PI1") (pin "21") (pinfunction "21_21") (pintype "passive"))
      (node (ref "PI1") (pin "24") (pinfunction "24_24") (pintype "passive"))
      (node (ref "PI1") (pin "31") (pinfunction "31_31") (pintype "passive"))
      (node (ref "PI1") (pin "34") (pinfunction "34_34") (pintype "passive"))
      (node (ref "PI1") (pin "41") (pinfunction "41_41") (pintype "passive"))
      (node (ref "PI1") (pin "44") (pinfunction "44_44") (pintype "passive"))
      (node (ref "PI1") (pin "51") (pinfunction "51_51") (pintype "passive"))
      (node (ref "PI1") (pin "54") (pinfunction "54_54") (pintype "passive"))
      (node (ref "PI1") (pin "59") (pinfunction "59_59") (pintype "passive"))
      (node (ref "PI1") (pin "60") (pinfunction "60_60") (pintype "passive"))
      (node (ref "PI1") (pin "65") (pinfunction "65_65") (pintype "passive"))
      (node (ref "PI1") (pin "66") (pinfunction "66_66") (pintype "passive"))
      (node (ref "PI1") (pin "7") (pinfunction "7_7") (pintype "passive"))
      (node (ref "PI1") (pin "72") (pinfunction "72_72") (pintype "passive"))
      (node (ref "PI1") (pin "73") (pinfunction "73_73") (pintype "passive"))
      (node (ref "PI1") (pin "8") (pinfunction "8_8") (pintype "passive"))
      (node (ref "PI1") (pin "97") (pinfunction "97_97") (pintype "passive"))
      (node (ref "R1") (pin "2") (pinfunction "2_2") (pintype "passive"))
      (node (ref "R11") (pin "2") (pinfunction "2_2") (pintype "passive"))
      (node (ref "R13") (pin "2") (pinfunction "2_2") (pintype "passive"))
      (node (ref "R2") (pin "2") (pinfunction "2_2") (pintype "passive"))
      (node (ref "SD1") (pin "MT1") (pinfunction "MT1_MT1") (pintype "bidirectional"))
      (node (ref "SD1") (pin "MT2") (pinfunction "MT2_MT2") (pintype "bidirectional"))
      (node (ref "SD1") (pin "MT3") (pinfunction "MT3_MT3") (pintype "bidirectional"))
      (node (ref "SD1") (pin "MT4") (pinfunction "MT4_MT4") (pintype "bidirectional"))
      (node (ref "SD1") (pin "VSS") (pinfunction "VSS_VSS") (pintype "bidirectional"))
      (node (ref "SW1") (pin "1") (pinfunction "1_1") (pintype "passive"))
      (node (ref "SW1") (pin "3") (pinfunction "3_3") (pintype "passive"))
      (node (ref "SW1") (pin "4") (pinfunction "4_4") (pintype "passive"))
      (node (ref "USBC") (pin "A1") (pinfunction "GND_A1") (pintype "passive"))
      (node (ref "USBC") (pin "A12") (pinfunction "GND1_A12") (pintype "passive"))
      (node (ref "USBC") (pin "B1") (pinfunction "GND3_B1") (pintype "passive"))
      (node (ref "USBC") (pin "B12") (pinfunction "GND2_B12") (pintype "passive"))
      (node (ref "USBC") (pin "S1") (pinfunction "SHIELD_S1") (pintype "passive"))
      (node (ref "USBC") (pin "S2") (pinfunction "SHIELD_S2") (pintype "passive"))
      (node (ref "USBC") (pin "S3") (pinfunction "SHIELD_S3") (pintype "passive"))
      (node (ref "USBC") (pin "S4") (pinfunction "SHIELD_S4") (pintype "passive"))
      (node (ref "X1") (pin "A10") (pinfunction "10_A10") (pintype "passive"))
      (node (ref "X1") (pin "A14") (pinfunction "14_A14") (pintype "passive"))
      (node (ref "X1") (pin "A15") (pinfunction "15_A15") (pintype "passive"))
      (node (ref "X1") (pin "A16") (pinfunction "16_A16") (pintype "passive"))
      (node (ref "X1") (pin "A25") (pinfunction "25_A25") (pintype "passive"))
      (node (ref "X1") (pin "A30") (pinfunction "30_A30") (pintype "passive"))
      (node (ref "X1") (pin "A31") (pinfunction "31_A31") (pintype "passive"))
      (node (ref "X1") (pin "A32") (pinfunction "32_A32") (pintype "passive"))
      (node (ref "X1") (pin "B10") (pinfunction "10_B10") (pintype "passive"))
      (node (ref "X1") (pin "B14") (pinfunction "14_B14") (pintype "passive"))
      (node (ref "X1") (pin "B15") (pinfunction "15_B15") (pintype "passive"))
      (node (ref "X1") (pin "B16") (pinfunction "16_B16") (pintype "passive"))
      (node (ref "X1") (pin "B19") (pinfunction "19_B19") (pintype "passive"))
      (node (ref "X1") (pin "B22") (pinfunction "22_B22") (pintype "passive"))
      (node (ref "X1") (pin "B25") (pinfunction "25_B25") (pintype "passive"))
      (node (ref "X1") (pin "B30") (pinfunction "30_B30") (pintype "passive"))
      (node (ref "X1") (pin "B31") (pinfunction "31_B31") (pintype "passive"))
      (node (ref "X1") (pin "B32") (pinfunction "32_B32") (pintype "passive"))
      (node (ref "X2") (pin "2") (pinfunction "VSS_2") (pintype "power_in"))
      (node (ref "X3") (pin "A10") (pinfunction "10_A10") (pintype "passive"))
      (node (ref "X3") (pin "A14") (pinfunction "14_A14") (pintype "passive"))
      (node (ref "X3") (pin "A15") (pinfunction "15_A15") (pintype "passive"))
      (node (ref "X3") (pin "A16") (pinfunction "16_A16") (pintype "passive"))
      (node (ref "X3") (pin "A25") (pinfunction "25_A25") (pintype "passive"))
      (node (ref "X3") (pin "A30") (pinfunction "30_A30") (pintype "passive"))
      (node (ref "X3") (pin "A31") (pinfunction "31_A31") (pintype "passive"))
      (node (ref "X3") (pin "A32") (pinfunction "32_A32") (pintype "passive"))
      (node (ref "X3") (pin "B10") (pinfunction "10_B10") (pintype "passive"))
      (node (ref "X3") (pin "B14") (pinfunction "14_B14") (pintype "passive"))
      (node (ref "X3") (pin "B15") (pinfunction "15_B15") (pintype "passive"))
      (node (ref "X3") (pin "B16") (pinfunction "16_B16") (pintype "passive"))
      (node (ref "X3") (pin "B19") (pinfunction "19_B19") (pintype "passive"))
      (node (ref "X3") (pin "B22") (pinfunction "22_B22") (pintype "passive"))
      (node (ref "X3") (pin "B25") (pinfunction "25_B25") (pintype "passive"))
      (node (ref "X3") (pin "B30") (pinfunction "30_B30") (pintype "passive"))
      (node (ref "X3") (pin "B31") (pinfunction "31_B31") (pintype "passive"))
      (node (ref "X3") (pin "B32") (pinfunction "32_B32") (pintype "passive"))
    )
    (net (code "39") (name "GPIO2") (class "Default")
      (node (ref "CON3") (pin "24") (pinfunction "24_24") (pintype "bidirectional"))
      (node (ref "GPIO") (pin "3") (pinfunction "3_3") (pintype "bidirectional"))
      (node (ref "PI1") (pin "57") (pinfunction "57_57") (pintype "passive"))
    )
    (net (code "40") (name "GPIO3") (class "Default")
      (node (ref "CON3") (pin "22") (pinfunction "22_22") (pintype "bidirectional"))
      (node (ref "GPIO") (pin "5") (pinfunction "5_5") (pintype "bidirectional"))
      (node (ref "PI1") (pin "55") (pinfunction "55_55") (pintype "passive"))
    )
    (net (code "41") (name "GPIO4") (class "Default")
      (node (ref "CON2") (pin "28") (pinfunction "28_28") (pintype "bidirectional"))
      (node (ref "GPIO") (pin "7") (pinfunction "7_7") (pintype "bidirectional"))
      (node (ref "PI1") (pin "53") (pinfunction "53_53") (pintype "passive"))
    )
    (net (code "42") (name "GPIO5") (class "Default")
      (node (ref "CON2") (pin "22") (pinfunction "22_22") (pintype "bidirectional"))
      (node (ref "GPIO") (pin "29") (pinfunction "29_29") (pintype "bidirectional"))
      (node (ref "PI1") (pin "33") (pinfunction "33_33") (pintype "passive"))
    )
    (net (code "43") (name "GPIO6") (class "Default")
      (node (ref "CON2") (pin "26") (pinfunction "26_26") (pintype "bidirectional"))
      (node (ref "CON3") (pin "30") (pinfunction "30_30") (pintype "bidirectional"))
      (node (ref "GPIO") (pin "31") (pinfunction "31_31") (pintype "bidirectional"))
      (node (ref "PI1") (pin "29") (pinfunction "29_29") (pintype "passive"))
    )
    (net (code "44") (name "GPIO7") (class "Default")
      (node (ref "CON3") (pin "4") (pinfunction "4_4") (pintype "bidirectional"))
      (node (ref "GPIO") (pin "26") (pinfunction "26_26") (pintype "bidirectional"))
      (node (ref "PI1") (pin "38") (pinfunction "38_38") (pintype "passive"))
    )
    (net (code "45") (name "GPIO8") (class "Default")
      (node (ref "CON3") (pin "6") (pinfunction "6_6") (pintype "bidirectional"))
      (node (ref "GPIO") (pin "24") (pinfunction "24_24") (pintype "bidirectional"))
      (node (ref "PI1") (pin "40") (pinfunction "40_40") (pintype "passive"))
    )
    (net (code "46") (name "GPIO9") (class "Default")
      (node (ref "CON3") (pin "12") (pinfunction "12_12") (pintype "bidirectional"))
      (node (ref "GPIO") (pin "21") (pinfunction "21_21") (pintype "bidirectional"))
      (node (ref "PI1") (pin "39") (pinfunction "39_39") (pintype "passive"))
    )
    (net (code "47") (name "GPIO10") (class "Default")
      (node (ref "CON3") (pin "10") (pinfunction "10_10") (pintype "bidirectional"))
      (node (ref "GPIO") (pin "19") (pinfunction "19_19") (pintype "bidirectional"))
      (node (ref "PI1") (pin "43") (pinfunction "43_43") (pintype "passive"))
    )
    (net (code "48") (name "GPIO11") (class "Default")
      (node (ref "CON3") (pin "8") (pinfunction "8_8") (pintype "bidirectional"))
      (node (ref "GPIO") (pin "23") (pinfunction "23_23") (pintype "bidirectional"))
      (node (ref "PI1") (pin "37") (pinfunction "37_37") (pintype "passive"))
    )
    (net (code "49") (name "GPIO12") (class "Default")
      (node (ref "CON2") (pin "18") (pinfunction "18_18") (pintype "bidirectional"))
      (node (ref "GPIO") (pin "32") (pinfunction "32_32") (pintype "bidirectional"))
      (node (ref "PI1") (pin "32") (pinfunction "32_32") (pintype "passive"))
    )
    (net (code "50") (name "GPIO13") (class "Default")
      (node (ref "CON2") (pin "24") (pinfunction "24_24") (pintype "bidirectional"))
      (node (ref "GPIO") (pin "33") (pinfunction "33_33") (pintype "bidirectional"))
      (node (ref "PI1") (pin "27") (pinfunction "27_27") (pintype "passive"))
    )
    (net (code "51") (name "GPIO14") (class "Default")
      (node (ref "CON3") (pin "18") (pinfunction "18_18") (pintype "bidirectional"))
      (node (ref "GPIO") (pin "8") (pinfunction "8_8") (pintype "bidirectional"))
      (node (ref "PI1") (pin "56") (pinfunction "56_56") (pintype "passive"))
    )
    (net (code "52") (name "GPIO15") (class "Default")
      (node (ref "CON3") (pin "20") (pinfunction "20_20") (pintype "bidirectional"))
      (node (ref "GPIO") (pin "10") (pinfunction "10_10") (pintype "bidirectional"))
      (node (ref "PI1") (pin "52") (pinfunction "52_52") (pintype "passive"))
    )
    (net (code "53") (name "GPIO16") (class "Default")
      (node (ref "CON2") (pin "36") (pinfunction "36_36") (pintype "bidirectional"))
      (node (ref "GPIO") (pin "36") (pinfunction "36_36") (pintype "bidirectional"))
      (node (ref "PI1") (pin "30") (pinfunction "30_30") (pintype "passive"))
    )
    (net (code "54") (name "GPIO17") (class "Default")
      (node (ref "CON2") (pin "38") (pinfunction "38_38") (pintype "bidirectional"))
      (node (ref "GPIO") (pin "11") (pinfunction "11_11") (pintype "bidirectional"))
      (node (ref "PI1") (pin "49") (pinfunction "49_49") (pintype "passive"))
    )
    (net (code "55") (name "GPIO18") (class "Default")
      (node (ref "CON2") (pin "40") (pinfunction "40_40") (pintype "bidirectional"))
      (node (ref "GPIO") (pin "12") (pinfunction "12_12") (pintype "bidirectional"))
      (node (ref "PI1") (pin "50") (pinfunction "50_50") (pintype "passive"))
    )
    (net (code "56") (name "GPIO19") (class "Default")
      (node (ref "CON2") (pin "30") (pinfunction "30_30") (pintype "bidirectional"))
      (node (ref "GPIO") (pin "35") (pinfunction "35_35") (pintype "bidirectional"))
      (node (ref "PI1") (pin "25") (pinfunction "25_25") (pintype "passive"))
    )
    (net (code "57") (name "GPIO20") (class "Default")
      (node (ref "CON2") (pin "32") (pinfunction "32_32") (pintype "bidirectional"))
      (node (ref "GPIO") (pin "38") (pinfunction "38_38") (pintype "bidirectional"))
      (node (ref "PI1") (pin "28") (pinfunction "28_28") (pintype "passive"))
    )
    (net (code "58") (name "GPIO21") (class "Default")
      (node (ref "CON2") (pin "34") (pinfunction "34_34") (pintype "bidirectional"))
      (node (ref "GPIO") (pin "40") (pinfunction "40_40") (pintype "bidirectional"))
      (node (ref "PI1") (pin "26") (pinfunction "26_26") (pintype "passive"))
    )
    (net (code "59") (name "GPIO22") (class "Default")
      (node (ref "CON3") (pin "32") (pinfunction "32_32") (pintype "bidirectional"))
      (node (ref "GPIO") (pin "15") (pinfunction "15_15") (pintype "bidirectional"))
      (node (ref "PI1") (pin "45") (pinfunction "45_45") (pintype "passive"))
    )
    (net (code "60") (name "GPIO23") (class "Default")
      (node (ref "GPIO") (pin "16") (pinfunction "16_16") (pintype "bidirectional"))
      (node (ref "PI1") (pin "48") (pinfunction "48_48") (pintype "passive"))
    )
    (net (code "61") (name "GPIO24") (class "Default")
      (node (ref "CON3") (pin "14") (pinfunction "14_14") (pintype "bidirectional"))
      (node (ref "GPIO") (pin "18") (pinfunction "18_18") (pintype "bidirectional"))
      (node (ref "PI1") (pin "46") (pinfunction "46_46") (pintype "passive"))
    )
    (net (code "62") (name "GPIO25") (class "Default")
      (node (ref "CON3") (pin "16") (pinfunction "16_16") (pintype "bidirectional"))
      (node (ref "GPIO") (pin "22") (pinfunction "22_22") (pintype "bidirectional"))
      (node (ref "PI1") (pin "42") (pinfunction "42_42") (pintype "passive"))
    )
    (net (code "63") (name "GPIO26") (class "Default")
      (node (ref "CON2") (pin "20") (pinfunction "20_20") (pintype "bidirectional"))
      (node (ref "GPIO") (pin "37") (pinfunction "37_37") (pintype "bidirectional"))
      (node (ref "PI1") (pin "23") (pinfunction "23_23") (pintype "passive"))
    )
    (net (code "64") (name "GPIO27") (class "Default")
      (node (ref "CON3") (pin "34") (pinfunction "34_34") (pintype "bidirectional"))
      (node (ref "GPIO") (pin "13") (pinfunction "13_13") (pintype "bidirectional"))
      (node (ref "PI1") (pin "47") (pinfunction "47_47") (pintype "passive"))
    )
    (net (code "65") (name "GPIO_VREF") (class "Default")
      (node (ref "PI1") (pin "77") (pinfunction "77_77") (pintype "passive"))
      (node (ref "R3") (pin "1") (pinfunction "1_1") (pintype "passive"))
      (node (ref "R4") (pin "1") (pinfunction "1_1") (pintype "passive"))
      (node (ref "R6") (pin "2") (pinfunction "2_2") (pintype "passive"))
      (node (ref "R7") (pin "2") (pinfunction "2_2") (pintype "passive"))
      (node (ref "TP-GREF") (pin "TP") (pinfunction "P$1_TP") (pintype "bidirectional"))
    )
    (net (code "66") (name "HDMI0_CEC") (class "Default")
      (node (ref "HDMI2") (pin "13") (pinfunction "GROUND_13") (pintype "passive"))
      (node (ref "PI1") (pin "152") (pinfunction "52_152") (pintype "passive"))
    )
    (net (code "67") (name "HDMI0_CK_N") (class "Default")
      (node (ref "HDMI2") (pin "12") (pinfunction "TMDSCLOCK-_12") (pintype "passive"))
      (node (ref "PI1") (pin "189") (pinfunction "89_189") (pintype "passive"))
    )
    (net (code "68") (name "HDMI0_CK_P") (class "Default")
      (node (ref "HDMI2") (pin "10") (pinfunction "TMDSCLOCKSHIELD_10") (pintype "passive"))
      (node (ref "PI1") (pin "187") (pinfunction "87_187") (pintype "passive"))
    )
    (net (code "69") (name "HDMI0_D0_N") (class "Default")
      (node (ref "HDMI2") (pin "9") (pinfunction "TMDS0-_9") (pintype "passive"))
      (node (ref "PI1") (pin "183") (pinfunction "83_183") (pintype "passive"))
    )
    (net (code "70") (name "HDMI0_D0_P") (class "Default")
      (node (ref "HDMI2") (pin "7") (pinfunction "TMDS0SHIELD_7") (pintype "passive"))
      (node (ref "PI1") (pin "181") (pinfunction "81_181") (pintype "passive"))
    )
    (net (code "71") (name "HDMI0_D1_N") (class "Default")
      (node (ref "HDMI2") (pin "6") (pinfunction "TMDS1-_6") (pintype "passive"))
      (node (ref "PI1") (pin "177") (pinfunction "77_177") (pintype "passive"))
    )
    (net (code "72") (name "HDMI0_D1_P") (class "Default")
      (node (ref "HDMI2") (pin "4") (pinfunction "TMDS1SHIELD_4") (pintype "passive"))
      (node (ref "PI1") (pin "175") (pinfunction "75_175") (pintype "passive"))
    )
    (net (code "73") (name "HDMI0_D2_N") (class "Default")
      (node (ref "HDMI2") (pin "3") (pinfunction "TMDS2-_3") (pintype "passive"))
      (node (ref "PI1") (pin "171") (pinfunction "71_171") (pintype "passive"))
    )
    (net (code "74") (name "HDMI0_D2_P") (class "Default")
      (node (ref "HDMI2") (pin "1") (pinfunction "TMDS2SHIELD_1") (pintype "passive"))
      (node (ref "PI1") (pin "169") (pinfunction "69_169") (pintype "passive"))
    )
    (net (code "75") (name "HDMI0_HOTPLUG") (class "Default")
      (node (ref "HDMI2") (pin "19") (pinfunction "HOTPLUG/HEC+_19") (pintype "passive"))
      (node (ref "PI1") (pin "154") (pinfunction "54_154") (pintype "passive"))
    )
    (net (code "76") (name "HDMI0_SCL") (class "Default")
      (node (ref "HDMI2") (pin "15") (pinfunction "SCL_15") (pintype "passive"))
      (node (ref "PI1") (pin "199") (pinfunction "99_199") (pintype "passive"))
    )
    (net (code "77") (name "HDMI0_SDA") (class "Default")
      (node (ref "HDMI2") (pin "16") (pinfunction "SDA_16") (pintype "passive"))
      (node (ref "PI1") (pin "200") (pinfunction "100_200") (pintype "passive"))
    )
    (net (code "78") (name "HDMI1_CEC") (class "Default")
      (node (ref "HDMI1") (pin "13") (pinfunction "GROUND_13") (pintype "passive"))
      (node (ref "PI1") (pin "150") (pinfunction "50_150") (pintype "passive"))
    )
    (net (code "79") (name "HDMI1_CK_N") (class "Default")
      (node (ref "HDMI1") (pin "12") (pinfunction "TMDSCLOCK-_12") (pintype "passive"))
      (node (ref "PI1") (pin "165") (pinfunction "65_165") (pintype "passive"))
    )
    (net (code "80") (name "HDMI1_CK_P") (class "Default")
      (node (ref "HDMI1") (pin "10") (pinfunction "TMDSCLOCKSHIELD_10") (pintype "passive"))
      (node (ref "PI1") (pin "163") (pinfunction "63_163") (pintype "passive"))
    )
    (net (code "81") (name "HDMI1_D0_N") (class "Default")
      (node (ref "HDMI1") (pin "9") (pinfunction "TMDS0-_9") (pintype "passive"))
      (node (ref "PI1") (pin "159") (pinfunction "59_159") (pintype "passive"))
    )
    (net (code "82") (name "HDMI1_D0_P") (class "Default")
      (node (ref "HDMI1") (pin "7") (pinfunction "TMDS0SHIELD_7") (pintype "passive"))
      (node (ref "PI1") (pin "157") (pinfunction "57_157") (pintype "passive"))
    )
    (net (code "83") (name "HDMI1_D1_N") (class "Default")
      (node (ref "HDMI1") (pin "6") (pinfunction "TMDS1-_6") (pintype "passive"))
      (node (ref "PI1") (pin "153") (pinfunction "53_153") (pintype "passive"))
    )
    (net (code "84") (name "HDMI1_D1_P") (class "Default")
      (node (ref "HDMI1") (pin "4") (pinfunction "TMDS1SHIELD_4") (pintype "passive"))
      (node (ref "PI1") (pin "151") (pinfunction "51_151") (pintype "passive"))
    )
    (net (code "85") (name "HDMI1_D2_N") (class "Default")
      (node (ref "HDMI1") (pin "3") (pinfunction "TMDS2-_3") (pintype "passive"))
      (node (ref "PI1") (pin "147") (pinfunction "47_147") (pintype "passive"))
    )
    (net (code "86") (name "HDMI1_D2_P") (class "Default")
      (node (ref "HDMI1") (pin "1") (pinfunction "TMDS2SHIELD_1") (pintype "passive"))
      (node (ref "PI1") (pin "145") (pinfunction "45_145") (pintype "passive"))
    )
    (net (code "87") (name "HDMI1_HOTPLUG") (class "Default")
      (node (ref "HDMI1") (pin "19") (pinfunction "HOTPLUG/HEC+_19") (pintype "passive"))
      (node (ref "PI1") (pin "144") (pinfunction "44_144") (pintype "passive"))
    )
    (net (code "88") (name "HDMI1_SCL") (class "Default")
      (node (ref "HDMI1") (pin "15") (pinfunction "SCL_15") (pintype "passive"))
      (node (ref "PI1") (pin "148") (pinfunction "48_148") (pintype "passive"))
    )
    (net (code "89") (name "HDMI1_SDA") (class "Default")
      (node (ref "HDMI1") (pin "16") (pinfunction "SDA_16") (pintype "passive"))
      (node (ref "PI1") (pin "146") (pinfunction "46_146") (pintype "passive"))
    )
    (net (code "90") (name "HDMI_5V") (class "Default")
      (node (ref "C4") (pin "1") (pinfunction "1_1") (pintype "passive"))
      (node (ref "HDMI1") (pin "18") (pinfunction "POWER_18") (pintype "power_in"))
      (node (ref "HDMI2") (pin "18") (pinfunction "POWER_18") (pintype "power_in"))
      (node (ref "IC4") (pin "2") (pinfunction "OUT_2") (pintype "power_in"))
      (node (ref "TP-5VHD") (pin "TP") (pinfunction "P$1_TP") (pintype "bidirectional"))
    )
    (net (code "91") (name "ID_SC") (class "Default")
      (node (ref "GPIO") (pin "28") (pinfunction "28_28") (pintype "bidirectional"))
      (node (ref "ID") (pin "1") (pinfunction "1_1") (pintype "bidirectional"))
      (node (ref "PI1") (pin "36") (pinfunction "36_36") (pintype "passive"))
    )
    (net (code "92") (name "ID_SD") (class "Default")
      (node (ref "GPIO") (pin "27") (pinfunction "27_27") (pintype "bidirectional"))
      (node (ref "ID") (pin "3") (pinfunction "3_3") (pintype "bidirectional"))
      (node (ref "PI1") (pin "35") (pinfunction "35_35") (pintype "passive"))
    )
    (net (code "93") (name "LED_NACT") (class "Default")
      (node (ref "PI1") (pin "22") (pinfunction "22_22") (pintype "passive"))
    )
    (net (code "94") (name "M2_3V3") (class "Default")
      (node (ref "C12") (pin "1") (pinfunction "1_1") (pintype "passive"))
      (node (ref "C13") (pin "1") (pinfunction "1_1") (pintype "passive"))
      (node (ref "C14") (pin "1") (pinfunction "1_1") (pintype "passive"))
      (node (ref "C15") (pin "1") (pinfunction "1_1") (pintype "passive"))
      (node (ref "C16") (pin "1") (pinfunction "1_1") (pintype "passive"))
      (node (ref "C17") (pin "1") (pinfunction "1_1") (pintype "passive"))
      (node (ref "L1") (pin "2") (pinfunction "2_2") (pintype "passive"))
      (node (ref "PCIE") (pin "12") (pinfunction "VCC3_12") (pintype "bidirectional"))
      (node (ref "PCIE") (pin "14") (pinfunction "VCC4_14") (pintype "bidirectional"))
      (node (ref "PCIE") (pin "16") (pinfunction "VCC5_16") (pintype "bidirectional"))
      (node (ref "PCIE") (pin "18") (pinfunction "VCC6_18") (pintype "bidirectional"))
      (node (ref "PCIE") (pin "2") (pinfunction "VCC1_2") (pintype "bidirectional"))
      (node (ref "PCIE") (pin "4") (pinfunction "VCC2_4") (pintype "bidirectional"))
      (node (ref "PCIE") (pin "70") (pinfunction "VCC7_70") (pintype "bidirectional"))
      (node (ref "PCIE") (pin "72") (pinfunction "VCC8_72") (pintype "bidirectional"))
      (node (ref "PCIE") (pin "74") (pinfunction "VCC9_74") (pintype "bidirectional"))
      (node (ref "R12") (pin "1") (pinfunction "1_1") (pintype "passive"))
      (node (ref "TP-VM2") (pin "TP") (pinfunction "P$1_TP") (pintype "bidirectional"))
      (node (ref "X2") (pin "3") (pinfunction "OUT_3") (pintype "output"))
      (node (ref "X2") (pin "4") (pinfunction "VDD_4") (pintype "power_in"))
    )
    (net (code "95") (name "MISO_SEL") (class "Default")
      (node (ref "CON2") (pin "23") (pinfunction "23_23") (pintype "bidirectional"))
      (node (ref "X1") (pin "A13") (pinfunction "13_A13") (pintype "passive"))
    )
    (net (code "96") (name "NPWR_LED") (class "Default")
      (node (ref "IC3") (pin "2") (pinfunction "A_2") (pintype "input"))
      (node (ref "PI1") (pin "96") (pinfunction "96_96") (pintype "passive"))
      (node (ref "TP-LED") (pin "TP") (pinfunction "P$1_TP") (pintype "bidirectional"))
    )
    (net (code "97") (name "NRPIBOOT") (class "Default")
      (node (ref "JP2") (pin "2") (pinfunction "2_2") (pintype "bidirectional"))
      (node (ref "PI1") (pin "94") (pinfunction "94_94") (pintype "passive"))
    )
    (net (code "98") (name "Net-(C11-Pad1)") (class "Default")
      (node (ref "C11") (pin "1") (pinfunction "1_1") (pintype "passive"))
      (node (ref "ETH1") (pin "CT1") (pinfunction "CT1_CT1") (pintype "bidirectional"))
      (node (ref "ETH1") (pin "CT2") (pinfunction "CT2_CT2") (pintype "bidirectional"))
      (node (ref "ETH1") (pin "CT3") (pinfunction "CT3_CT3") (pintype "bidirectional"))
      (node (ref "ETH1") (pin "CT4") (pinfunction "CT4_CT4") (pintype "bidirectional"))
    )
    (net (code "99") (name "Net-(ETH1-P17)") (class "Default")
      (node (ref "ETH1") (pin "17") (pinfunction "P17_17") (pintype "bidirectional"))
      (node (ref "R9") (pin "1") (pinfunction "1_1") (pintype "passive"))
    )
    (net (code "100") (name "Net-(ETH1-P19)") (class "Default")
      (node (ref "ETH1") (pin "19") (pinfunction "P19_19") (pintype "bidirectional"))
      (node (ref "R8") (pin "2") (pinfunction "2_2") (pintype "passive"))
    )
    (net (code "101") (name "Net-(IC2-ILIM)") (class "Default")
      (node (ref "IC2") (pin "5") (pinfunction "ILIM_5") (pintype "bidirectional"))
      (node (ref "R2") (pin "1") (pinfunction "1_1") (pintype "passive"))
    )
    (net (code "102") (name "Net-(IC3-Y)") (class "Default")
      (node (ref "IC3") (pin "4") (pinfunction "Y_4") (pintype "output"))
      (node (ref "R5") (pin "2") (pinfunction "2_2") (pintype "passive"))
    )
    (net (code "103") (name "Net-(IC5-FB)") (class "Default")
      (node (ref "C13") (pin "2") (pinfunction "2_2") (pintype "passive"))
      (node (ref "IC5") (pin "1") (pinfunction "FB_1") (pintype "bidirectional"))
      (node (ref "R12") (pin "2") (pinfunction "2_2") (pintype "passive"))
      (node (ref "R13") (pin "1") (pinfunction "1_1") (pintype "passive"))
      (node (ref "TP-M2FB") (pin "TP") (pinfunction "P$1_TP") (pintype "bidirectional"))
    )
    (net (code "104") (name "Net-(IC5-LX)") (class "Default")
      (node (ref "IC5") (pin "6") (pinfunction "LX_6") (pintype "power_in"))
      (node (ref "L1") (pin "1") (pinfunction "1_1") (pintype "passive"))
      (node (ref "TP-LX") (pin "TP") (pinfunction "P$1_TP") (pintype "bidirectional"))
    )
    (net (code "105") (name "Net-(J4-Pad17)") (class "Default")
      (node (ref "J4") (pin "17") (pinfunction "17_17") (pintype "passive"))
      (node (ref "R61") (pin "1") (pinfunction "1_1") (pintype "passive"))
    )
    (net (code "106") (name "Net-(LED1-PadC)") (class "Default")
      (node (ref "LED1") (pin "C") (pinfunction "C_C") (pintype "passive"))
      (node (ref "R5") (pin "1") (pinfunction "1_1") (pintype "passive"))
    )
    (net (code "107") (name "Net-(LED2-PadC)") (class "Default")
      (node (ref "LED2") (pin "C") (pinfunction "C_C") (pintype "passive"))
      (node (ref "R10") (pin "1") (pinfunction "1_1") (pintype "passive"))
    )
    (net (code "108") (name "Net-(PCIE-DA5{slash}~{DSS}{slash}~{LED1})") (class "Default")
      (node (ref "PCIE") (pin "10") (pinfunction "DA5/~{DSS}/~{LED1}_10") (pintype "bidirectional"))
      (node (ref "R10") (pin "2") (pinfunction "2_2") (pintype "passive"))
    )
    (net (code "109") (name "Net-(PCIE-SUSCLK)") (class "Default")
      (node (ref "PCIE") (pin "68") (pinfunction "SUSCLK_68") (pintype "bidirectional"))
      (node (ref "TP-M2CLK") (pin "TP") (pinfunction "P$1_TP") (pintype "bidirectional"))
      (node (ref "X2") (pin "1") (pinfunction "CON_1") (pintype "input"))
    )
    (net (code "110") (name "PCIE_CLK_N") (class "Default")
      (node (ref "PCIE") (pin "53") (pinfunction "REFCLK_N_53") (pintype "bidirectional"))
      (node (ref "PI1") (pin "111") (pinfunction "11_111") (pintype "passive"))
    )
    (net (code "111") (name "PCIE_CLK_P") (class "Default")
      (node (ref "PCIE") (pin "55") (pinfunction "REFCLK_P_55") (pintype "bidirectional"))
      (node (ref "PI1") (pin "109") (pinfunction "9_109") (pintype "passive"))
    )
    (net (code "112") (name "PCIE_NCLKREQ") (class "Default")
      (node (ref "PCIE") (pin "52") (pinfunction "~{CLKREQ}_52") (pintype "bidirectional"))
      (node (ref "PI1") (pin "101") (pinfunction "1_101") (pintype "passive"))
    )
    (net (code "113") (name "PCIE_NRST") (class "Default")
      (node (ref "PCIE") (pin "50") (pinfunction "~{PERST}_50") (pintype "bidirectional"))
      (node (ref "PI1") (pin "110") (pinfunction "10_110") (pintype "passive"))
    )
    (net (code "114") (name "PCIE_NWAKE") (class "Default")
      (node (ref "PCIE") (pin "54") (pinfunction "~{PEWAKE}_54") (pintype "bidirectional"))
      (node (ref "PI1") (pin "103") (pinfunction "3_103") (pintype "passive"))
    )
    (net (code "115") (name "PCIE_PWR_EN") (class "Default")
      (node (ref "IC5") (pin "7") (pinfunction "EN_7") (pintype "bidirectional"))
      (node (ref "PI1") (pin "105") (pinfunction "5_105") (pintype "passive"))
      (node (ref "R11") (pin "1") (pinfunction "1_1") (pintype "passive"))
    )
    (net (code "116") (name "PCIE_RX_N") (class "Default")
      (node (ref "PCIE") (pin "43") (pinfunction "PET_P0_43") (pintype "bidirectional"))
      (node (ref "PI1") (pin "117") (pinfunction "17_117") (pintype "passive"))
    )
    (net (code "117") (name "PCIE_RX_P") (class "Default")
      (node (ref "PCIE") (pin "41") (pinfunction "PET_N0_41") (pintype "bidirectional"))
      (node (ref "PI1") (pin "115") (pinfunction "15_115") (pintype "passive"))
    )
    (net (code "118") (name "PCIE_TX_N") (class "Default")
      (node (ref "PCIE") (pin "49") (pinfunction "PER_P0_49") (pintype "bidirectional"))
      (node (ref "PI1") (pin "123") (pinfunction "23_123") (pintype "passive"))
    )
    (net (code "119") (name "PCIE_TX_P") (class "Default")
      (node (ref "PCIE") (pin "47") (pinfunction "PER_N0_47") (pintype "bidirectional"))
      (node (ref "PI1") (pin "121") (pinfunction "21_121") (pintype "passive"))
    )
    (net (code "120") (name "PMIC_ENABLE") (class "Default")
      (node (ref "JP2") (pin "12") (pinfunction "12_12") (pintype "bidirectional"))
      (node (ref "PI1") (pin "100") (pinfunction "100_100") (pintype "passive"))
    )
    (net (code "121") (name "PWM") (class "Default")
      (node (ref "FAN") (pin "3") (pinfunction "P$3_3") (pintype "bidirectional"))
      (node (ref "PI1") (pin "20") (pinfunction "20_20") (pintype "passive"))
    )
    (net (code "122") (name "PWR_BUT") (class "Default")
      (node (ref "JP2") (pin "14") (pinfunction "14_14") (pintype "bidirectional"))
      (node (ref "PI1") (pin "91") (pinfunction "91_91") (pintype "passive"))
      (node (ref "SW1") (pin "2") (pinfunction "2_2") (pintype "passive"))
      (node (ref "TP-BTN") (pin "TP") (pinfunction "P$1_TP") (pintype "bidirectional"))
    )
    (net (code "123") (name "RP2040_RST0") (class "Default")
      (node (ref "CON3") (pin "23") (pinfunction "23_23") (pintype "bidirectional"))
      (node (ref "X1") (pin "B18") (pinfunction "18_B18") (pintype "passive"))
    )
    (net (code "124") (name "RP2040_RST1") (class "Default")
      (node (ref "CON3") (pin "21") (pinfunction "21_21") (pintype "bidirectional"))
      (node (ref "X3") (pin "B18") (pinfunction "18_B18") (pintype "passive"))
    )
    (net (code "125") (name "SCL0") (class "Default")
      (node (ref "J3") (pin "20") (pinfunction "20_20") (pintype "passive"))
      (node (ref "PI1") (pin "79") (pinfunction "79_79") (pintype "passive"))
    )
    (net (code "126") (name "SCL1") (class "Default")
      (node (ref "ID") (pin "2") (pinfunction "2_2") (pintype "bidirectional"))
      (node (ref "J4") (pin "20") (pinfunction "20_20") (pintype "passive"))
      (node (ref "R4") (pin "2") (pinfunction "2_2") (pintype "passive"))
    )
    (net (code "127") (name "SDA0") (class "Default")
      (node (ref "J3") (pin "21") (pinfunction "21_21") (pintype "passive"))
      (node (ref "PI1") (pin "81") (pinfunction "81_81") (pintype "passive"))
    )
    (net (code "128") (name "SDA1") (class "Default")
      (node (ref "ID") (pin "4") (pinfunction "4_4") (pintype "bidirectional"))
      (node (ref "J4") (pin "21") (pinfunction "21_21") (pintype "passive"))
      (node (ref "R3") (pin "2") (pinfunction "2_2") (pintype "passive"))
    )
    (net (code "129") (name "SDO_A_0") (class "Default")
      (node (ref "CON2") (pin "15") (pinfunction "15_15") (pintype "bidirectional"))
      (node (ref "X1") (pin "A17") (pinfunction "17_A17") (pintype "passive"))
    )
    (net (code "130") (name "SDO_A_1") (class "Default")
      (node (ref "CON2") (pin "13") (pinfunction "13_13") (pintype "bidirectional"))
      (node (ref "X1") (pin "A18") (pinfunction "18_A18") (pintype "passive"))
    )
    (net (code "131") (name "SDO_A_2") (class "Default")
      (node (ref "CON2") (pin "11") (pinfunction "11_11") (pintype "bidirectional"))
      (node (ref "X1") (pin "A19") (pinfunction "19_A19") (pintype "passive"))
    )
    (net (code "132") (name "SDO_A_3") (class "Default")
      (node (ref "CON2") (pin "9") (pinfunction "9_9") (pintype "bidirectional"))
      (node (ref "X1") (pin "A20") (pinfunction "20_A20") (pintype "passive"))
    )
    (net (code "133") (name "SDO_B_0") (class "Default")
      (node (ref "CON2") (pin "7") (pinfunction "7_7") (pintype "bidirectional"))
      (node (ref "X1") (pin "A21") (pinfunction "21_A21") (pintype "passive"))
    )
    (net (code "134") (name "SDO_B_1") (class "Default")
      (node (ref "CON2") (pin "5") (pinfunction "5_5") (pintype "bidirectional"))
      (node (ref "X1") (pin "A22") (pinfunction "22_A22") (pintype "passive"))
    )
    (net (code "135") (name "SDO_B_2") (class "Default")
      (node (ref "CON2") (pin "3") (pinfunction "3_3") (pintype "bidirectional"))
      (node (ref "X1") (pin "A23") (pinfunction "23_A23") (pintype "passive"))
    )
    (net (code "136") (name "SDO_B_3") (class "Default")
      (node (ref "CON2") (pin "1") (pinfunction "1_1") (pintype "bidirectional"))
      (node (ref "X1") (pin "A24") (pinfunction "24_A24") (pintype "passive"))
    )
    (net (code "137") (name "SD_CLK") (class "Default")
      (node (ref "PI1") (pin "58") (pinfunction "58_58") (pintype "passive"))
      (node (ref "SD1") (pin "CLK") (pinfunction "CLK_CLK") (pintype "bidirectional"))
    )
    (net (code "138") (name "SD_CMD") (class "Default")
      (node (ref "PI1") (pin "61") (pinfunction "61_61") (pintype "passive"))
      (node (ref "SD1") (pin "CMD") (pinfunction "CMD_CMD") (pintype "bidirectional"))
    )
    (net (code "139") (name "SD_DAT0") (class "Default")
      (node (ref "PI1") (pin "64") (pinfunction "64_64") (pintype "passive"))
      (node (ref "SD1") (pin "DAT0") (pinfunction "DAT0_DAT0") (pintype "bidirectional"))
    )
    (net (code "140") (name "SD_DAT1") (class "Default")
      (node (ref "PI1") (pin "68") (pinfunction "68_68") (pintype "passive"))
      (node (ref "SD1") (pin "DAT1") (pinfunction "DAT1_DAT1") (pintype "bidirectional"))
    )
    (net (code "141") (name "SD_DAT2") (class "Default")
      (node (ref "PI1") (pin "70") (pinfunction "70_70") (pintype "passive"))
      (node (ref "SD1") (pin "DAT2") (pinfunction "DAT2_DAT2") (pintype "bidirectional"))
    )
    (net (code "142") (name "SD_DAT3") (class "Default")
      (node (ref "PI1") (pin "62") (pinfunction "62_62") (pintype "passive"))
      (node (ref "SD1") (pin "DAT3/CD") (pinfunction "CD/DAT3_DAT3/CD") (pintype "bidirectional"))
    )
    (net (code "143") (name "SD_PWR") (class "Default")
      (node (ref "C10") (pin "1") (pinfunction "1_1") (pintype "passive"))
      (node (ref "IC1") (pin "1") (pinfunction "OUT_1") (pintype "power_in"))
      (node (ref "SD1") (pin "VDD") (pinfunction "VDD_VDD") (pintype "bidirectional"))
      (node (ref "TP-VSD") (pin "TP") (pinfunction "P$1_TP") (pintype "bidirectional"))
    )
    (net (code "144") (name "SD_PWR_ON") (class "Default")
      (node (ref "IC1") (pin "4") (pinfunction "EN_4") (pintype "bidirectional"))
      (node (ref "PI1") (pin "76") (pinfunction "76_76") (pintype "passive"))
    )
    (net (code "145") (name "SPI_ADC_CS") (class "Default")
      (node (ref "CON2") (pin "39") (pinfunction "39_39") (pintype "bidirectional"))
      (node (ref "X1") (pin "A2") (pinfunction "2_A2") (pintype "passive"))
    )
    (net (code "146") (name "SPI_AIOMODULE_CS0") (class "Default")
      (node (ref "CON3") (pin "5") (pinfunction "5_5") (pintype "bidirectional"))
      (node (ref "X1") (pin "A29") (pinfunction "29_A29") (pintype "passive"))
      (node (ref "X1") (pin "B29") (pinfunction "29_B29") (pintype "passive"))
    )
    (net (code "147") (name "SPI_AIOMODULE_MISO") (class "Default")
      (node (ref "CON3") (pin "11") (pinfunction "11_11") (pintype "bidirectional"))
      (node (ref "X1") (pin "A26") (pinfunction "26_A26") (pintype "passive"))
      (node (ref "X1") (pin "B26") (pinfunction "26_B26") (pintype "passive"))
    )
    (net (code "148") (name "SPI_AIOMODULE_MOSI") (class "Default")
      (node (ref "CON3") (pin "9") (pinfunction "9_9") (pintype "bidirectional"))
      (node (ref "X1") (pin "A27") (pinfunction "27_A27") (pintype "passive"))
      (node (ref "X1") (pin "B27") (pinfunction "27_B27") (pintype "passive"))
    )
    (net (code "149") (name "SPI_AIOMODULE_SCK") (class "Default")
      (node (ref "CON3") (pin "7") (pinfunction "7_7") (pintype "bidirectional"))
      (node (ref "X1") (pin "A28") (pinfunction "28_A28") (pintype "passive"))
      (node (ref "X1") (pin "B28") (pinfunction "28_B28") (pintype "passive"))
    )
    (net (code "150") (name "SPI_DAC_CS") (class "Default")
      (node (ref "CON2") (pin "21") (pinfunction "21_21") (pintype "bidirectional"))
      (node (ref "X1") (pin "B2") (pinfunction "2_B2") (pintype "passive"))
    )
    (net (code "151") (name "SPI_DIOMODULE_CS1") (class "Default")
      (node (ref "CON3") (pin "3") (pinfunction "3_3") (pintype "bidirectional"))
      (node (ref "X3") (pin "A29") (pinfunction "29_A29") (pintype "passive"))
      (node (ref "X3") (pin "B29") (pinfunction "29_B29") (pintype "passive"))
    )
    (net (code "152") (name "SPI_DIOMODULE_MISO") (class "Default")
      (node (ref "X3") (pin "A26") (pinfunction "26_A26") (pintype "passive"))
      (node (ref "X3") (pin "B26") (pinfunction "26_B26") (pintype "passive"))
    )
    (net (code "153") (name "SPI_DIOMODULE_MOSI") (class "Default")
      (node (ref "X3") (pin "A27") (pinfunction "27_A27") (pintype "passive"))
      (node (ref "X3") (pin "B27") (pinfunction "27_B27") (pintype "passive"))
    )
    (net (code "154") (name "SPI_DIOMODULE_SCK") (class "Default")
      (node (ref "X3") (pin "A28") (pinfunction "28_A28") (pintype "passive"))
      (node (ref "X3") (pin "B28") (pinfunction "28_B28") (pintype "passive"))
    )
    (net (code "155") (name "SPI_DIO_CS0") (class "Default")
      (node (ref "CON3") (pin "33") (pinfunction "33_33") (pintype "bidirectional"))
      (node (ref "X3") (pin "A2") (pinfunction "2_A2") (pintype "passive"))
    )
    (net (code "156") (name "SPI_DIO_CS1") (class "Default")
      (node (ref "CON3") (pin "31") (pinfunction "31_31") (pintype "bidirectional"))
      (node (ref "X3") (pin "A3") (pinfunction "3_A3") (pintype "passive"))
    )
    (net (code "157") (name "SPI_MISO") (class "Default")
      (node (ref "CON2") (pin "29") (pinfunction "29_29") (pintype "bidirectional"))
      (node (ref "X1") (pin "A7") (pinfunction "7_A7") (pintype "passive"))
      (node (ref "X1") (pin "B7") (pinfunction "7_B7") (pintype "passive"))
      (node (ref "X3") (pin "A7") (pinfunction "7_A7") (pintype "passive"))
      (node (ref "X3") (pin "B7") (pinfunction "7_B7") (pintype "passive"))
    )
    (net (code "158") (name "SPI_MOSI") (class "Default")
      (node (ref "CON2") (pin "31") (pinfunction "31_31") (pintype "bidirectional"))
      (node (ref "X1") (pin "A6") (pinfunction "6_A6") (pintype "passive"))
      (node (ref "X1") (pin "B6") (pinfunction "6_B6") (pintype "passive"))
      (node (ref "X3") (pin "A6") (pinfunction "6_A6") (pintype "passive"))
      (node (ref "X3") (pin "B6") (pinfunction "6_B6") (pintype "passive"))
    )
    (net (code "159") (name "SPI_PGA_CS0") (class "Default")
      (node (ref "CON2") (pin "37") (pinfunction "37_37") (pintype "bidirectional"))
      (node (ref "X1") (pin "A3") (pinfunction "3_A3") (pintype "passive"))
    )
    (net (code "160") (name "SPI_PGA_CS1") (class "Default")
      (node (ref "CON2") (pin "35") (pinfunction "35_35") (pintype "bidirectional"))
      (node (ref "X1") (pin "A4") (pinfunction "4_A4") (pintype "passive"))
    )
    (net (code "161") (name "SPI_SCK") (class "Default")
      (node (ref "CON2") (pin "33") (pinfunction "33_33") (pintype "bidirectional"))
      (node (ref "X1") (pin "A5") (pinfunction "5_A5") (pintype "passive"))
      (node (ref "X1") (pin "B5") (pinfunction "5_B5") (pintype "passive"))
      (node (ref "X3") (pin "A5") (pinfunction "5_A5") (pintype "passive"))
      (node (ref "X3") (pin "B5") (pinfunction "5_B5") (pintype "passive"))
    )
    (net (code "162") (name "SWCLK") (class "Default")
      (node (ref "CON3") (pin "15") (pinfunction "15_15") (pintype "bidirectional"))
      (node (ref "X1") (pin "B23") (pinfunction "23_B23") (pintype "passive"))
      (node (ref "X3") (pin "B23") (pinfunction "23_B23") (pintype "passive"))
    )
    (net (code "163") (name "SWDIO") (class "Default")
      (node (ref "CON3") (pin "13") (pinfunction "13_13") (pintype "bidirectional"))
      (node (ref "X1") (pin "B24") (pinfunction "24_B24") (pintype "passive"))
      (node (ref "X3") (pin "B24") (pinfunction "24_B24") (pintype "passive"))
    )
    (net (code "164") (name "SYNC_OUT") (class "Default")
      (node (ref "JP2") (pin "6") (pinfunction "6_6") (pintype "bidirectional"))
      (node (ref "PI1") (pin "17") (pinfunction "17_17") (pintype "passive"))
    )
    (net (code "165") (name "TACHO") (class "Default")
      (node (ref "FAN") (pin "1") (pinfunction "P$1_1") (pintype "bidirectional"))
      (node (ref "PI1") (pin "15") (pinfunction "15_15") (pintype "passive"))
    )
    (net (code "166") (name "TR0_TAP") (class "Default")
      (node (ref "ETH1") (pin "VC1") (pinfunction "VC1_VC1") (pintype "bidirectional"))
      (node (ref "POE") (pin "3") (pinfunction "3_3") (pintype "bidirectional"))
    )
    (net (code "167") (name "TR1_TAP") (class "Default")
      (node (ref "ETH1") (pin "VC2") (pinfunction "VC2_VC2") (pintype "bidirectional"))
      (node (ref "POE") (pin "1") (pinfunction "1_1") (pintype "bidirectional"))
    )
    (net (code "168") (name "TR2_TAP") (class "Default")
      (node (ref "ETH1") (pin "VC3") (pinfunction "VC3_VC3") (pintype "bidirectional"))
      (node (ref "POE") (pin "2") (pinfunction "2_2") (pintype "bidirectional"))
    )
    (net (code "169") (name "TR3_TAP") (class "Default")
      (node (ref "ETH1") (pin "VC4") (pinfunction "VC4_VC4") (pintype "bidirectional"))
      (node (ref "POE") (pin "4") (pinfunction "4_4") (pintype "bidirectional"))
    )
    (net (code "170") (name "TRD0_N") (class "Default")
      (node (ref "D2") (pin "2") (pinfunction "D1-_2") (pintype "bidirectional"))
      (node (ref "D2") (pin "9") (pinfunction "D1-_9") (pintype "bidirectional"))
      (node (ref "ETH1") (pin "TD1-") (pinfunction "TD1-_TD1-") (pintype "bidirectional"))
      (node (ref "PI1") (pin "9") (pinfunction "9_9") (pintype "passive"))
    )
    (net (code "171") (name "TRD0_P") (class "Default")
      (node (ref "D2") (pin "1") (pinfunction "D1+_1") (pintype "bidirectional"))
      (node (ref "D2") (pin "10") (pinfunction "D1+_10") (pintype "bidirectional"))
      (node (ref "ETH1") (pin "TD1+") (pinfunction "TD1+_TD1+") (pintype "bidirectional"))
      (node (ref "PI1") (pin "11") (pinfunction "11_11") (pintype "passive"))
    )
    (net (code "172") (name "TRD1_N") (class "Default")
      (node (ref "D2") (pin "4") (pinfunction "D2+_4") (pintype "bidirectional"))
      (node (ref "D2") (pin "7") (pinfunction "D2+_7") (pintype "bidirectional"))
      (node (ref "ETH1") (pin "TD2-") (pinfunction "TD2-_TD2-") (pintype "bidirectional"))
      (node (ref "PI1") (pin "5") (pinfunction "5_5") (pintype "passive"))
    )
    (net (code "173") (name "TRD1_P") (class "Default")
      (node (ref "D2") (pin "5") (pinfunction "D2-_5") (pintype "bidirectional"))
      (node (ref "D2") (pin "6") (pinfunction "D2-_6") (pintype "bidirectional"))
      (node (ref "ETH1") (pin "TD2+") (pinfunction "TD2+_TD2+") (pintype "bidirectional"))
      (node (ref "PI1") (pin "3") (pinfunction "3_3") (pintype "passive"))
    )
    (net (code "174") (name "TRD2_N") (class "Default")
      (node (ref "D1") (pin "4") (pinfunction "D2+_4") (pintype "bidirectional"))
      (node (ref "D1") (pin "7") (pinfunction "D2+_7") (pintype "bidirectional"))
      (node (ref "ETH1") (pin "TD3-") (pinfunction "TD3-_TD3-") (pintype "bidirectional"))
      (node (ref "PI1") (pin "10") (pinfunction "10_10") (pintype "passive"))
    )
    (net (code "175") (name "TRD2_P") (class "Default")
      (node (ref "D1") (pin "5") (pinfunction "D2-_5") (pintype "bidirectional"))
      (node (ref "D1") (pin "6") (pinfunction "D2-_6") (pintype "bidirectional"))
      (node (ref "ETH1") (pin "TD3+") (pinfunction "TD3+_TD3+") (pintype "bidirectional"))
      (node (ref "PI1") (pin "12") (pinfunction "12_12") (pintype "passive"))
    )
    (net (code "176") (name "TRD3_N") (class "Default")
      (node (ref "D1") (pin "2") (pinfunction "D1-_2") (pintype "bidirectional"))
      (node (ref "D1") (pin "9") (pinfunction "D1-_9") (pintype "bidirectional"))
      (node (ref "ETH1") (pin "TD4-") (pinfunction "TD4-_TD4-") (pintype "bidirectional"))
      (node (ref "PI1") (pin "6") (pinfunction "6_6") (pintype "passive"))
    )
    (net (code "177") (name "TRD3_P") (class "Default")
      (node (ref "D1") (pin "1") (pinfunction "D1+_1") (pintype "bidirectional"))
      (node (ref "D1") (pin "10") (pinfunction "D1+_10") (pintype "bidirectional"))
      (node (ref "ETH1") (pin "TD4+") (pinfunction "TD4+_TD4+") (pintype "bidirectional"))
      (node (ref "PI1") (pin "4") (pinfunction "4_4") (pintype "passive"))
    )
    (net (code "178") (name "UART0_RX") (class "Default")
      (node (ref "CON3") (pin "19") (pinfunction "19_19") (pintype "bidirectional"))
      (node (ref "X1") (pin "B20") (pinfunction "20_B20") (pintype "passive"))
      (node (ref "X3") (pin "B20") (pinfunction "20_B20") (pintype "passive"))
    )
    (net (code "179") (name "UART0_TX") (class "Default")
      (node (ref "CON3") (pin "17") (pinfunction "17_17") (pintype "bidirectional"))
      (node (ref "X1") (pin "B21") (pinfunction "21_B21") (pintype "passive"))
      (node (ref "X3") (pin "B21") (pinfunction "21_B21") (pintype "passive"))
    )
    (net (code "180") (name "USB2_N") (class "Default")
      (node (ref "PI1") (pin "104") (pinfunction "4_104") (pintype "passive"))
      (node (ref "USBC") (pin "A7") (pinfunction "D-1_A7") (pintype "passive"))
      (node (ref "USBC") (pin "B7") (pinfunction "D-2_B7") (pintype "passive"))
    )
    (net (code "181") (name "USB2_P") (class "Default")
      (node (ref "PI1") (pin "106") (pinfunction "6_106") (pintype "passive"))
      (node (ref "USBC") (pin "A6") (pinfunction "D+1_A6") (pintype "passive"))
      (node (ref "USBC") (pin "B6") (pinfunction "D+2_B6") (pintype "passive"))
    )
    (net (code "182") (name "USB3-0-D_N") (class "Default")
      (node (ref "J1") (pin "2") (pinfunction "D-_2") (pintype "passive"))
      (node (ref "PI1") (pin "135") (pinfunction "35_135") (pintype "passive"))
    )
    (net (code "183") (name "USB3-0-D_P") (class "Default")
      (node (ref "J1") (pin "3") (pinfunction "D+_3") (pintype "passive"))
      (node (ref "PI1") (pin "133") (pinfunction "33_133") (pintype "passive"))
    )
    (net (code "184") (name "USB3-0-RX_N") (class "Default")
      (node (ref "J1") (pin "5") (pinfunction "STDA_SSRX-_5") (pintype "passive"))
      (node (ref "PI1") (pin "127") (pinfunction "27_127") (pintype "passive"))
    )
    (net (code "185") (name "USB3-0-RX_P") (class "Default")
      (node (ref "J1") (pin "6") (pinfunction "STDA_SSRX+_6") (pintype "passive"))
      (node (ref "PI1") (pin "129") (pinfunction "29_129") (pintype "passive"))
    )
    (net (code "186") (name "USB3-0-TX_N") (class "Default")
      (node (ref "J1") (pin "8") (pinfunction "STDA_SSTX-_8") (pintype "passive"))
      (node (ref "PI1") (pin "139") (pinfunction "39_139") (pintype "passive"))
    )
    (net (code "187") (name "USB3-0-TX_P") (class "Default")
      (node (ref "J1") (pin "9") (pinfunction "STDA_SSTX+_9") (pintype "passive"))
      (node (ref "PI1") (pin "141") (pinfunction "41_141") (pintype "passive"))
    )
    (net (code "188") (name "USB3-1-D_N") (class "Default")
      (node (ref "J2") (pin "2") (pinfunction "D-_2") (pintype "passive"))
      (node (ref "PI1") (pin "166") (pinfunction "66_166") (pintype "passive"))
    )
    (net (code "189") (name "USB3-1-D_P") (class "Default")
      (node (ref "J2") (pin "3") (pinfunction "D+_3") (pintype "passive"))
      (node (ref "PI1") (pin "164") (pinfunction "64_164") (pintype "passive"))
    )
    (net (code "190") (name "USB3-1-RX_N") (class "Default")
      (node (ref "J2") (pin "5") (pinfunction "STDA_SSRX-_5") (pintype "passive"))
      (node (ref "PI1") (pin "158") (pinfunction "58_158") (pintype "passive"))
    )
    (net (code "191") (name "USB3-1-RX_P") (class "Default")
      (node (ref "J2") (pin "6") (pinfunction "STDA_SSRX+_6") (pintype "passive"))
      (node (ref "PI1") (pin "160") (pinfunction "60_160") (pintype "passive"))
    )
    (net (code "192") (name "USB3-1-TX_N") (class "Default")
      (node (ref "J2") (pin "8") (pinfunction "STDA_SSTX-_8") (pintype "passive"))
      (node (ref "PI1") (pin "170") (pinfunction "70_170") (pintype "passive"))
    )
    (net (code "193") (name "USB3-1-TX_P") (class "Default")
      (node (ref "J2") (pin "9") (pinfunction "STDA_SSTX+_9") (pintype "passive"))
      (node (ref "PI1") (pin "172") (pinfunction "72_172") (pintype "passive"))
    )
    (net (code "194") (name "USBOTG_ID") (class "Default")
      (node (ref "JP2") (pin "10") (pinfunction "10_10") (pintype "bidirectional"))
      (node (ref "PI1") (pin "102") (pinfunction "2_102") (pintype "passive"))
    )
    (net (code "195") (name "VBAT") (class "Default")
      (node (ref "PI1") (pin "75") (pinfunction "75_75") (pintype "passive"))
    )
    (net (code "196") (name "VBUS") (class "Default")
      (node (ref "C6") (pin "1") (pinfunction "1_1") (pintype "passive"))
      (node (ref "C7") (pin "1") (pinfunction "1_1") (pintype "passive"))
      (node (ref "C8") (pin "1") (pinfunction "1_1") (pintype "passive"))
      (node (ref "IC2") (pin "6") (pinfunction "OUT_6") (pintype "bidirectional"))
      (node (ref "J1") (pin "1") (pinfunction "VBUS_1") (pintype "passive"))
      (node (ref "J2") (pin "1") (pinfunction "VBUS_1") (pintype "passive"))
      (node (ref "TP-VBUS") (pin "TP") (pinfunction "P$1_TP") (pintype "bidirectional"))
    )
    (net (code "197") (name "VBUS_EN") (class "Default")
      (node (ref "IC2") (pin "3") (pinfunction "EN_3") (pintype "bidirectional"))
      (node (ref "PI1") (pin "112") (pinfunction "12_112") (pintype "passive"))
    )
    (net (code "198") (name "WL_NDIS") (class "Default")
      (node (ref "JP3") (pin "1") (pinfunction "1_1") (pintype "bidirectional"))
      (node (ref "PI1") (pin "90") (pinfunction "90_90") (pintype "passive"))
    )
    (net (code "199") (name "unconnected-(CON2-Pad2)") (class "Default")
      (node (ref "CON2") (pin "2") (pinfunction "2_2") (pintype "bidirectional"))
    )
    (net (code "200") (name "unconnected-(CON2-Pad4)") (class "Default")
      (node (ref "CON2") (pin "4") (pinfunction "4_4") (pintype "bidirectional"))
    )
    (net (code "201") (name "unconnected-(CON2-Pad6)") (class "Default")
      (node (ref "CON2") (pin "6") (pinfunction "6_6") (pintype "bidirectional"))
    )
    (net (code "202") (name "unconnected-(CON2-Pad8)") (class "Default")
      (node (ref "CON2") (pin "8") (pinfunction "8_8") (pintype "bidirectional"))
    )
    (net (code "203") (name "unconnected-(CON2-Pad10)") (class "Default")
      (node (ref "CON2") (pin "10") (pinfunction "10_10") (pintype "bidirectional"))
    )
    (net (code "204") (name "unconnected-(CON2-Pad12)") (class "Default")
      (node (ref "CON2") (pin "12") (pinfunction "12_12") (pintype "bidirectional"))
    )
    (net (code "205") (name "unconnected-(CON2-Pad14)") (class "Default")
      (node (ref "CON2") (pin "14") (pinfunction "14_14") (pintype "bidirectional"))
    )
    (net (code "206") (name "unconnected-(CON2-Pad16)") (class "Default")
      (node (ref "CON2") (pin "16") (pinfunction "16_16") (pintype "bidirectional"))
    )
    (net (code "207") (name "unconnected-(CON3-Pad26)") (class "Default")
      (node (ref "CON3") (pin "26") (pinfunction "26_26") (pintype "bidirectional"))
    )
    (net (code "208") (name "unconnected-(CON3-Pad28)") (class "Default")
      (node (ref "CON3") (pin "28") (pinfunction "28_28") (pintype "bidirectional"))
    )
    (net (code "209") (name "unconnected-(CON3-Pad35)") (class "Default")
      (node (ref "CON3") (pin "35") (pinfunction "35_35") (pintype "bidirectional"))
    )
    (net (code "210") (name "unconnected-(CON3-Pad36)") (class "Default")
      (node (ref "CON3") (pin "36") (pinfunction "36_36") (pintype "bidirectional"))
    )
    (net (code "211") (name "unconnected-(CON3-Pad37)") (class "Default")
      (node (ref "CON3") (pin "37") (pinfunction "37_37") (pintype "bidirectional"))
    )
    (net (code "212") (name "unconnected-(CON3-Pad38)") (class "Default")
      (node (ref "CON3") (pin "38") (pinfunction "38_38") (pintype "bidirectional"))
    )
    (net (code "213") (name "unconnected-(CON3-Pad39)") (class "Default")
      (node (ref "CON3") (pin "39") (pinfunction "39_39") (pintype "bidirectional"))
    )
    (net (code "214") (name "unconnected-(CON3-Pad40)") (class "Default")
      (node (ref "CON3") (pin "40") (pinfunction "40_40") (pintype "bidirectional"))
    )
    (net (code "215") (name "unconnected-(HDMI1-CEC-Pad14)") (class "Default")
      (node (ref "HDMI1") (pin "14") (pinfunction "CEC_14") (pintype "passive"))
    )
    (net (code "216") (name "unconnected-(HDMI2-CEC-Pad14)") (class "Default")
      (node (ref "HDMI2") (pin "14") (pinfunction "CEC_14") (pintype "passive"))
    )
    (net (code "217") (name "unconnected-(IC1-NFLG-Pad3)") (class "Default")
      (node (ref "IC1") (pin "3") (pinfunction "NFLG_3") (pintype "bidirectional"))
    )
    (net (code "218") (name "unconnected-(IC2-~{FAULT}-Pad4)") (class "Default")
      (node (ref "IC2") (pin "4") (pinfunction "~{FAULT}_4") (pintype "bidirectional"))
    )
    (net (code "219") (name "unconnected-(IC5-NC-Pad5)") (class "Default")
      (node (ref "IC5") (pin "5") (pinfunction "NC_5") (pintype "no_connect"))
    )
    (net (code "220") (name "unconnected-(IC5-PG-Pad2)") (class "Default")
      (node (ref "IC5") (pin "2") (pinfunction "PG_2") (pintype "bidirectional"))
    )
    (net (code "221") (name "unconnected-(J4-Pad18)") (class "Default")
      (node (ref "J4") (pin "18") (pinfunction "18_18") (pintype "passive"))
    )
    (net (code "222") (name "unconnected-(JP2-Pad8)") (class "Default")
      (node (ref "JP2") (pin "8") (pinfunction "8_8") (pintype "bidirectional"))
    )
    (net (code "223") (name "unconnected-(PCIE-DEVSLP-Pad38)") (class "Default")
      (node (ref "PCIE") (pin "38") (pinfunction "DEVSLP_38") (pintype "bidirectional"))
    )
    (net (code "224") (name "unconnected-(PCIE-NC1-Pad58)") (class "Default")
      (node (ref "PCIE") (pin "58") (pinfunction "NC1_58") (pintype "bidirectional"))
    )
    (net (code "225") (name "unconnected-(PCIE-NC2-Pad56)") (class "Default")
      (node (ref "PCIE") (pin "56") (pinfunction "NC2_56") (pintype "bidirectional"))
    )
    (net (code "226") (name "unconnected-(PCIE-NC3-Pad48)") (class "Default")
      (node (ref "PCIE") (pin "48") (pinfunction "NC3_48") (pintype "bidirectional"))
    )
    (net (code "227") (name "unconnected-(PCIE-NC4-Pad46)") (class "Default")
      (node (ref "PCIE") (pin "46") (pinfunction "NC4_46") (pintype "bidirectional"))
    )
    (net (code "228") (name "unconnected-(PCIE-NC5-Pad44)") (class "Default")
      (node (ref "PCIE") (pin "44") (pinfunction "NC5_44") (pintype "bidirectional"))
    )
    (net (code "229") (name "unconnected-(PCIE-NC6-Pad42)") (class "Default")
      (node (ref "PCIE") (pin "42") (pinfunction "NC6_42") (pintype "bidirectional"))
    )
    (net (code "230") (name "unconnected-(PCIE-NC7-Pad40)") (class "Default")
      (node (ref "PCIE") (pin "40") (pinfunction "NC7_40") (pintype "bidirectional"))
    )
    (net (code "231") (name "unconnected-(PCIE-NC8-Pad36)") (class "Default")
      (node (ref "PCIE") (pin "36") (pinfunction "NC8_36") (pintype "bidirectional"))
    )
    (net (code "232") (name "unconnected-(PCIE-NC9-Pad34)") (class "Default")
      (node (ref "PCIE") (pin "34") (pinfunction "NC9_34") (pintype "bidirectional"))
    )
    (net (code "233") (name "unconnected-(PCIE-NC10-Pad32)") (class "Default")
      (node (ref "PCIE") (pin "32") (pinfunction "NC10_32") (pintype "bidirectional"))
    )
    (net (code "234") (name "unconnected-(PCIE-NC11-Pad30)") (class "Default")
      (node (ref "PCIE") (pin "30") (pinfunction "NC11_30") (pintype "bidirectional"))
    )
    (net (code "235") (name "unconnected-(PCIE-NC12-Pad28)") (class "Default")
      (node (ref "PCIE") (pin "28") (pinfunction "NC12_28") (pintype "bidirectional"))
    )
    (net (code "236") (name "unconnected-(PCIE-NC13-Pad26)") (class "Default")
      (node (ref "PCIE") (pin "26") (pinfunction "NC13_26") (pintype "bidirectional"))
    )
    (net (code "237") (name "unconnected-(PCIE-NC14-Pad24)") (class "Default")
      (node (ref "PCIE") (pin "24") (pinfunction "NC14_24") (pintype "bidirectional"))
    )
    (net (code "238") (name "unconnected-(PCIE-NC15-Pad22)") (class "Default")
      (node (ref "PCIE") (pin "22") (pinfunction "NC15_22") (pintype "bidirectional"))
    )
    (net (code "239") (name "unconnected-(PCIE-NC16-Pad20)") (class "Default")
      (node (ref "PCIE") (pin "20") (pinfunction "NC16_20") (pintype "bidirectional"))
    )
    (net (code "240") (name "unconnected-(PCIE-NC17-Pad8)") (class "Default")
      (node (ref "PCIE") (pin "8") (pinfunction "NC17_8") (pintype "bidirectional"))
    )
    (net (code "241") (name "unconnected-(PCIE-NC18-Pad6)") (class "Default")
      (node (ref "PCIE") (pin "6") (pinfunction "NC18_6") (pintype "bidirectional"))
    )
    (net (code "242") (name "unconnected-(PCIE-NC19-Pad67)") (class "Default")
      (node (ref "PCIE") (pin "67") (pinfunction "NC19_67") (pintype "bidirectional"))
    )
    (net (code "243") (name "unconnected-(PCIE-PEDET-Pad69)") (class "Default")
      (node (ref "PCIE") (pin "69") (pinfunction "PEDET_69") (pintype "bidirectional"))
    )
    (net (code "244") (name "unconnected-(PCIE-PER_N1-Pad35)") (class "Default")
      (node (ref "PCIE") (pin "35") (pinfunction "PER_N1_35") (pintype "bidirectional"))
    )
    (net (code "245") (name "unconnected-(PCIE-PER_N2-Pad23)") (class "Default")
      (node (ref "PCIE") (pin "23") (pinfunction "PER_N2_23") (pintype "bidirectional"))
    )
    (net (code "246") (name "unconnected-(PCIE-PER_N3-Pad11)") (class "Default")
      (node (ref "PCIE") (pin "11") (pinfunction "PER_N3_11") (pintype "bidirectional"))
    )
    (net (code "247") (name "unconnected-(PCIE-PER_P1-Pad37)") (class "Default")
      (node (ref "PCIE") (pin "37") (pinfunction "PER_P1_37") (pintype "bidirectional"))
    )
    (net (code "248") (name "unconnected-(PCIE-PER_P2-Pad25)") (class "Default")
      (node (ref "PCIE") (pin "25") (pinfunction "PER_P2_25") (pintype "bidirectional"))
    )
    (net (code "249") (name "unconnected-(PCIE-PER_P3-Pad13)") (class "Default")
      (node (ref "PCIE") (pin "13") (pinfunction "PER_P3_13") (pintype "bidirectional"))
    )
    (net (code "250") (name "unconnected-(PCIE-PET_N1-Pad29)") (class "Default")
      (node (ref "PCIE") (pin "29") (pinfunction "PET_N1_29") (pintype "bidirectional"))
    )
    (net (code "251") (name "unconnected-(PCIE-PET_N2-Pad17)") (class "Default")
      (node (ref "PCIE") (pin "17") (pinfunction "PET_N2_17") (pintype "bidirectional"))
    )
    (net (code "252") (name "unconnected-(PCIE-PET_N3-Pad5)") (class "Default")
      (node (ref "PCIE") (pin "5") (pinfunction "PET_N3_5") (pintype "bidirectional"))
    )
    (net (code "253") (name "unconnected-(PCIE-PET_P1-Pad31)") (class "Default")
      (node (ref "PCIE") (pin "31") (pinfunction "PET_P1_31") (pintype "bidirectional"))
    )
    (net (code "254") (name "unconnected-(PCIE-PET_P2-Pad19)") (class "Default")
      (node (ref "PCIE") (pin "19") (pinfunction "PET_P2_19") (pintype "bidirectional"))
    )
    (net (code "255") (name "unconnected-(PCIE-PET_P3-Pad7)") (class "Default")
      (node (ref "PCIE") (pin "7") (pinfunction "PET_P3_7") (pintype "bidirectional"))
    )
    (net (code "256") (name "unconnected-(PI1-Pad63)") (class "Default")
      (node (ref "PI1") (pin "63") (pinfunction "63_63") (pintype "passive"))
    )
    (net (code "257") (name "unconnected-(PI1-Pad67)") (class "Default")
      (node (ref "PI1") (pin "67") (pinfunction "67_67") (pintype "passive"))
    )
    (net (code "258") (name "unconnected-(PI1-Pad69)") (class "Default")
      (node (ref "PI1") (pin "69") (pinfunction "69_69") (pintype "passive"))
    )
    (net (code "259") (name "unconnected-(PI1-Pad71)") (class "Default")
      (node (ref "PI1") (pin "71") (pinfunction "71_71") (pintype "passive"))
    )
    (net (code "260") (name "unconnected-(PI1-Pad74)") (class "Default")
      (node (ref "PI1") (pin "74") (pinfunction "74_74") (pintype "passive"))
    )
    (net (code "261") (name "unconnected-(SD1-DET_A-PadDET1)") (class "Default")
      (node (ref "SD1") (pin "DET1") (pinfunction "DET_A_DET1") (pintype "bidirectional"))
    )
    (net (code "262") (name "unconnected-(SD1-DET_B-PadDET2)") (class "Default")
      (node (ref "SD1") (pin "DET2") (pinfunction "DET_B_DET2") (pintype "bidirectional"))
    )
    (net (code "263") (name "unconnected-(USBC-SBU1-PadA8)") (class "Default")
      (node (ref "USBC") (pin "A8") (pinfunction "SBU1_A8") (pintype "passive"))
    )
    (net (code "264") (name "unconnected-(USBC-SBU2-PadB8)") (class "Default")
      (node (ref "USBC") (pin "B8") (pinfunction "SBU2_B8") (pintype "passive"))
    )
    (net (code "265") (name "unconnected-(X1B-3-PadB3)") (class "Default")
      (node (ref "X1") (pin "B3") (pinfunction "3_B3") (pintype "passive"))
    )
    (net (code "266") (name "unconnected-(X1B-4-PadB4)") (class "Default")
      (node (ref "X1") (pin "B4") (pinfunction "4_B4") (pintype "passive"))
    )
    (net (code "267") (name "unconnected-(X1B-11-PadB11)") (class "Default")
      (node (ref "X1") (pin "B11") (pinfunction "11_B11") (pintype "passive"))
    )
    (net (code "268") (name "unconnected-(X1B-17-PadB17)") (class "Default")
      (node (ref "X1") (pin "B17") (pinfunction "17_B17") (pintype "passive"))
    )
    (net (code "269") (name "unconnected-(X3A-4-PadA4)") (class "Default")
      (node (ref "X3") (pin "A4") (pinfunction "4_A4") (pintype "passive"))
    )
    (net (code "270") (name "unconnected-(X3A-17-PadA17)") (class "Default")
      (node (ref "X3") (pin "A17") (pinfunction "17_A17") (pintype "passive"))
    )
    (net (code "271") (name "unconnected-(X3A-18-PadA18)") (class "Default")
      (node (ref "X3") (pin "A18") (pinfunction "18_A18") (pintype "passive"))
    )
    (net (code "272") (name "unconnected-(X3A-19-PadA19)") (class "Default")
      (node (ref "X3") (pin "A19") (pinfunction "19_A19") (pintype "passive"))
    )
    (net (code "273") (name "unconnected-(X3A-20-PadA20)") (class "Default")
      (node (ref "X3") (pin "A20") (pinfunction "20_A20") (pintype "passive"))
    )
    (net (code "274") (name "unconnected-(X3A-21-PadA21)") (class "Default")
      (node (ref "X3") (pin "A21") (pinfunction "21_A21") (pintype "passive"))
    )
    (net (code "275") (name "unconnected-(X3A-22-PadA22)") (class "Default")
      (node (ref "X3") (pin "A22") (pinfunction "22_A22") (pintype "passive"))
    )
    (net (code "276") (name "unconnected-(X3A-23-PadA23)") (class "Default")
      (node (ref "X3") (pin "A23") (pinfunction "23_A23") (pintype "passive"))
    )
    (net (code "277") (name "unconnected-(X3A-24-PadA24)") (class "Default")
      (node (ref "X3") (pin "A24") (pinfunction "24_A24") (pintype "passive"))
    )
    (net (code "278") (name "unconnected-(X3B-2-PadB2)") (class "Default")
      (node (ref "X3") (pin "B2") (pinfunction "2_B2") (pintype "passive"))
    )
    (net (code "279") (name "unconnected-(X3B-3-PadB3)") (class "Default")
      (node (ref "X3") (pin "B3") (pinfunction "3_B3") (pintype "passive"))
    )
    (net (code "280") (name "unconnected-(X3B-4-PadB4)") (class "Default")
      (node (ref "X3") (pin "B4") (pinfunction "4_B4") (pintype "passive"))
    )
    (net (code "281") (name "unconnected-(X3B-11-PadB11)") (class "Default")
      (node (ref "X3") (pin "B11") (pinfunction "11_B11") (pintype "passive"))
    )
    (net (code "282") (name "unconnected-(X3B-12-PadB12)") (class "Default")
      (node (ref "X3") (pin "B12") (pinfunction "12_B12") (pintype "passive"))
    )
    (net (code "283") (name "unconnected-(X3B-13-PadB13)") (class "Default")
      (node (ref "X3") (pin "B13") (pinfunction "13_B13") (pintype "passive"))
    )
    (net (code "284") (name "unconnected-(X3B-17-PadB17)") (class "Default")
      (node (ref "X3") (pin "B17") (pinfunction "17_B17") (pintype "passive"))
    )
    (net (code "285") (name "~{ADC_RST}") (class "Default")
      (node (ref "CON2") (pin "25") (pinfunction "25_25") (pintype "bidirectional"))
      (node (ref "X1") (pin "A12") (pinfunction "12_A12") (pintype "passive"))
    )
  )
)
